# fmc.net
KiCad netlist of a schematic drawn in EAGLE
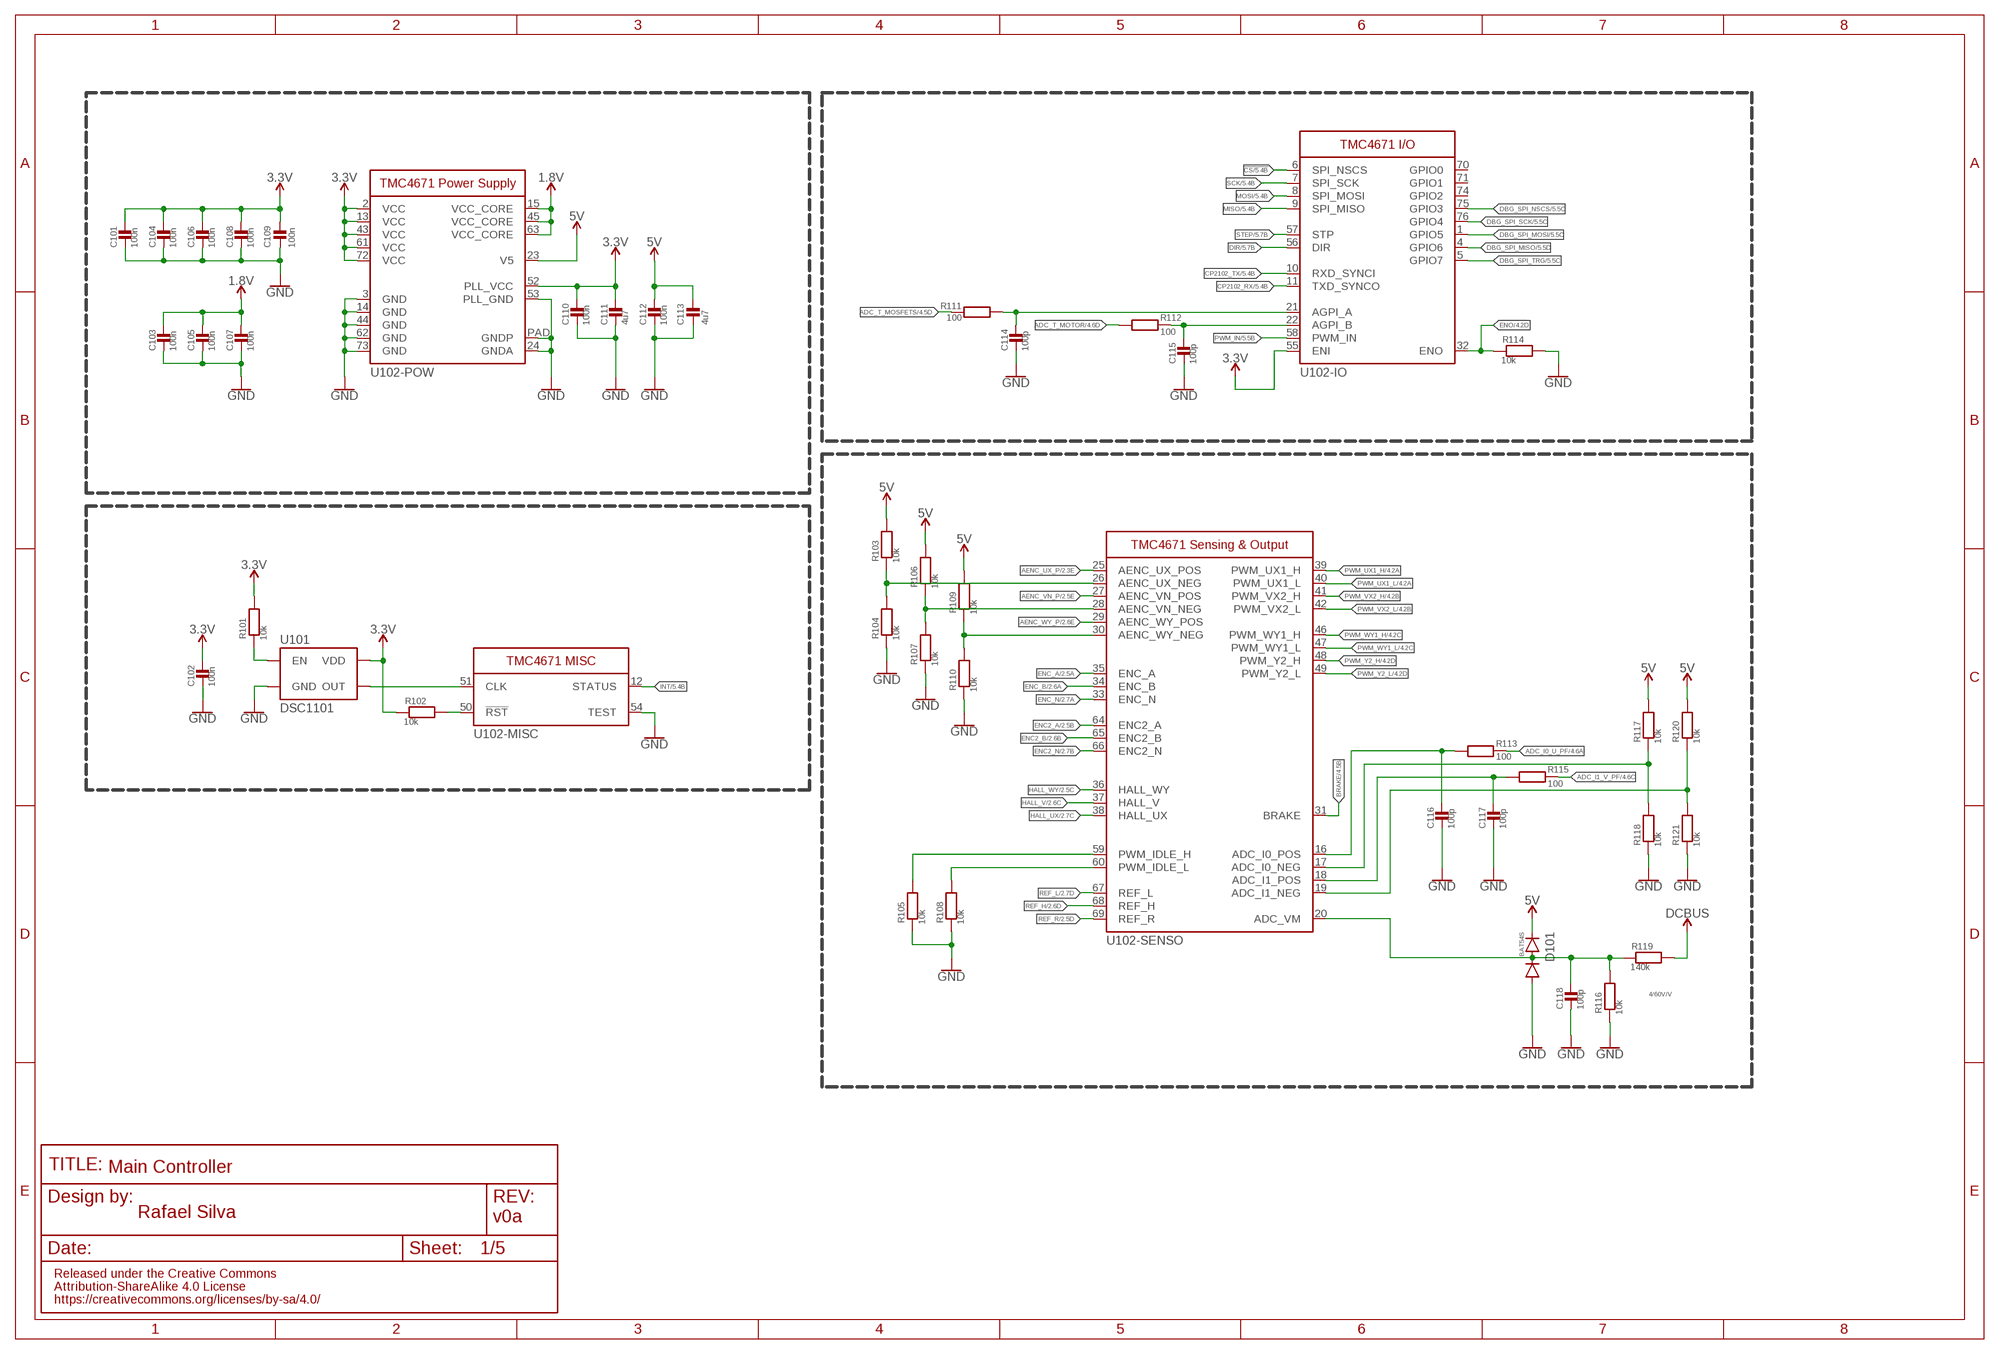
[diagram p0: schematic, sheet 1]
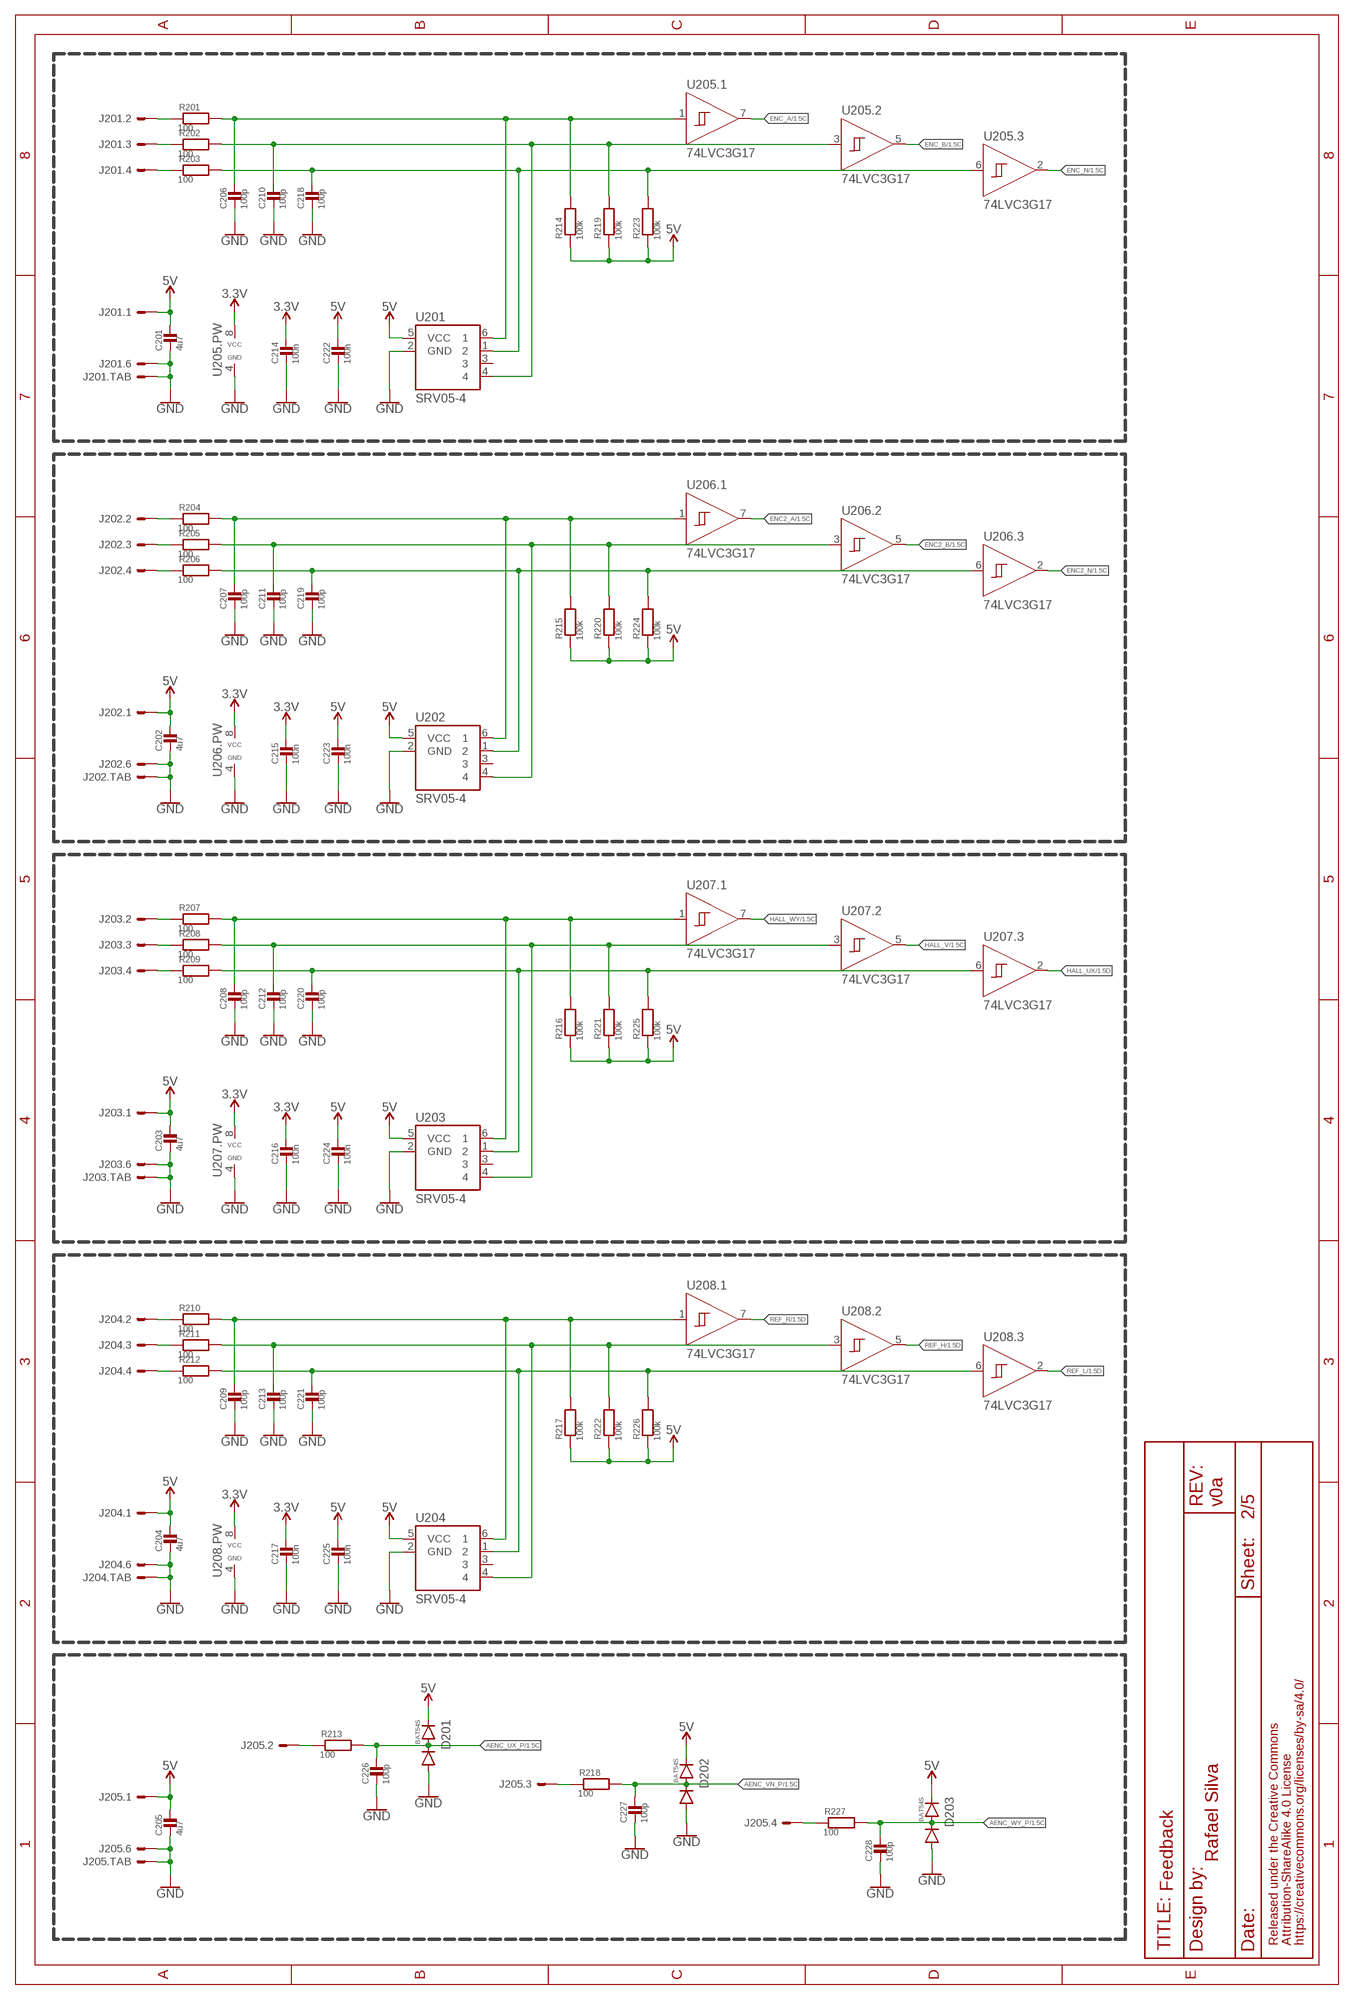
[diagram p1: schematic, sheet 2]
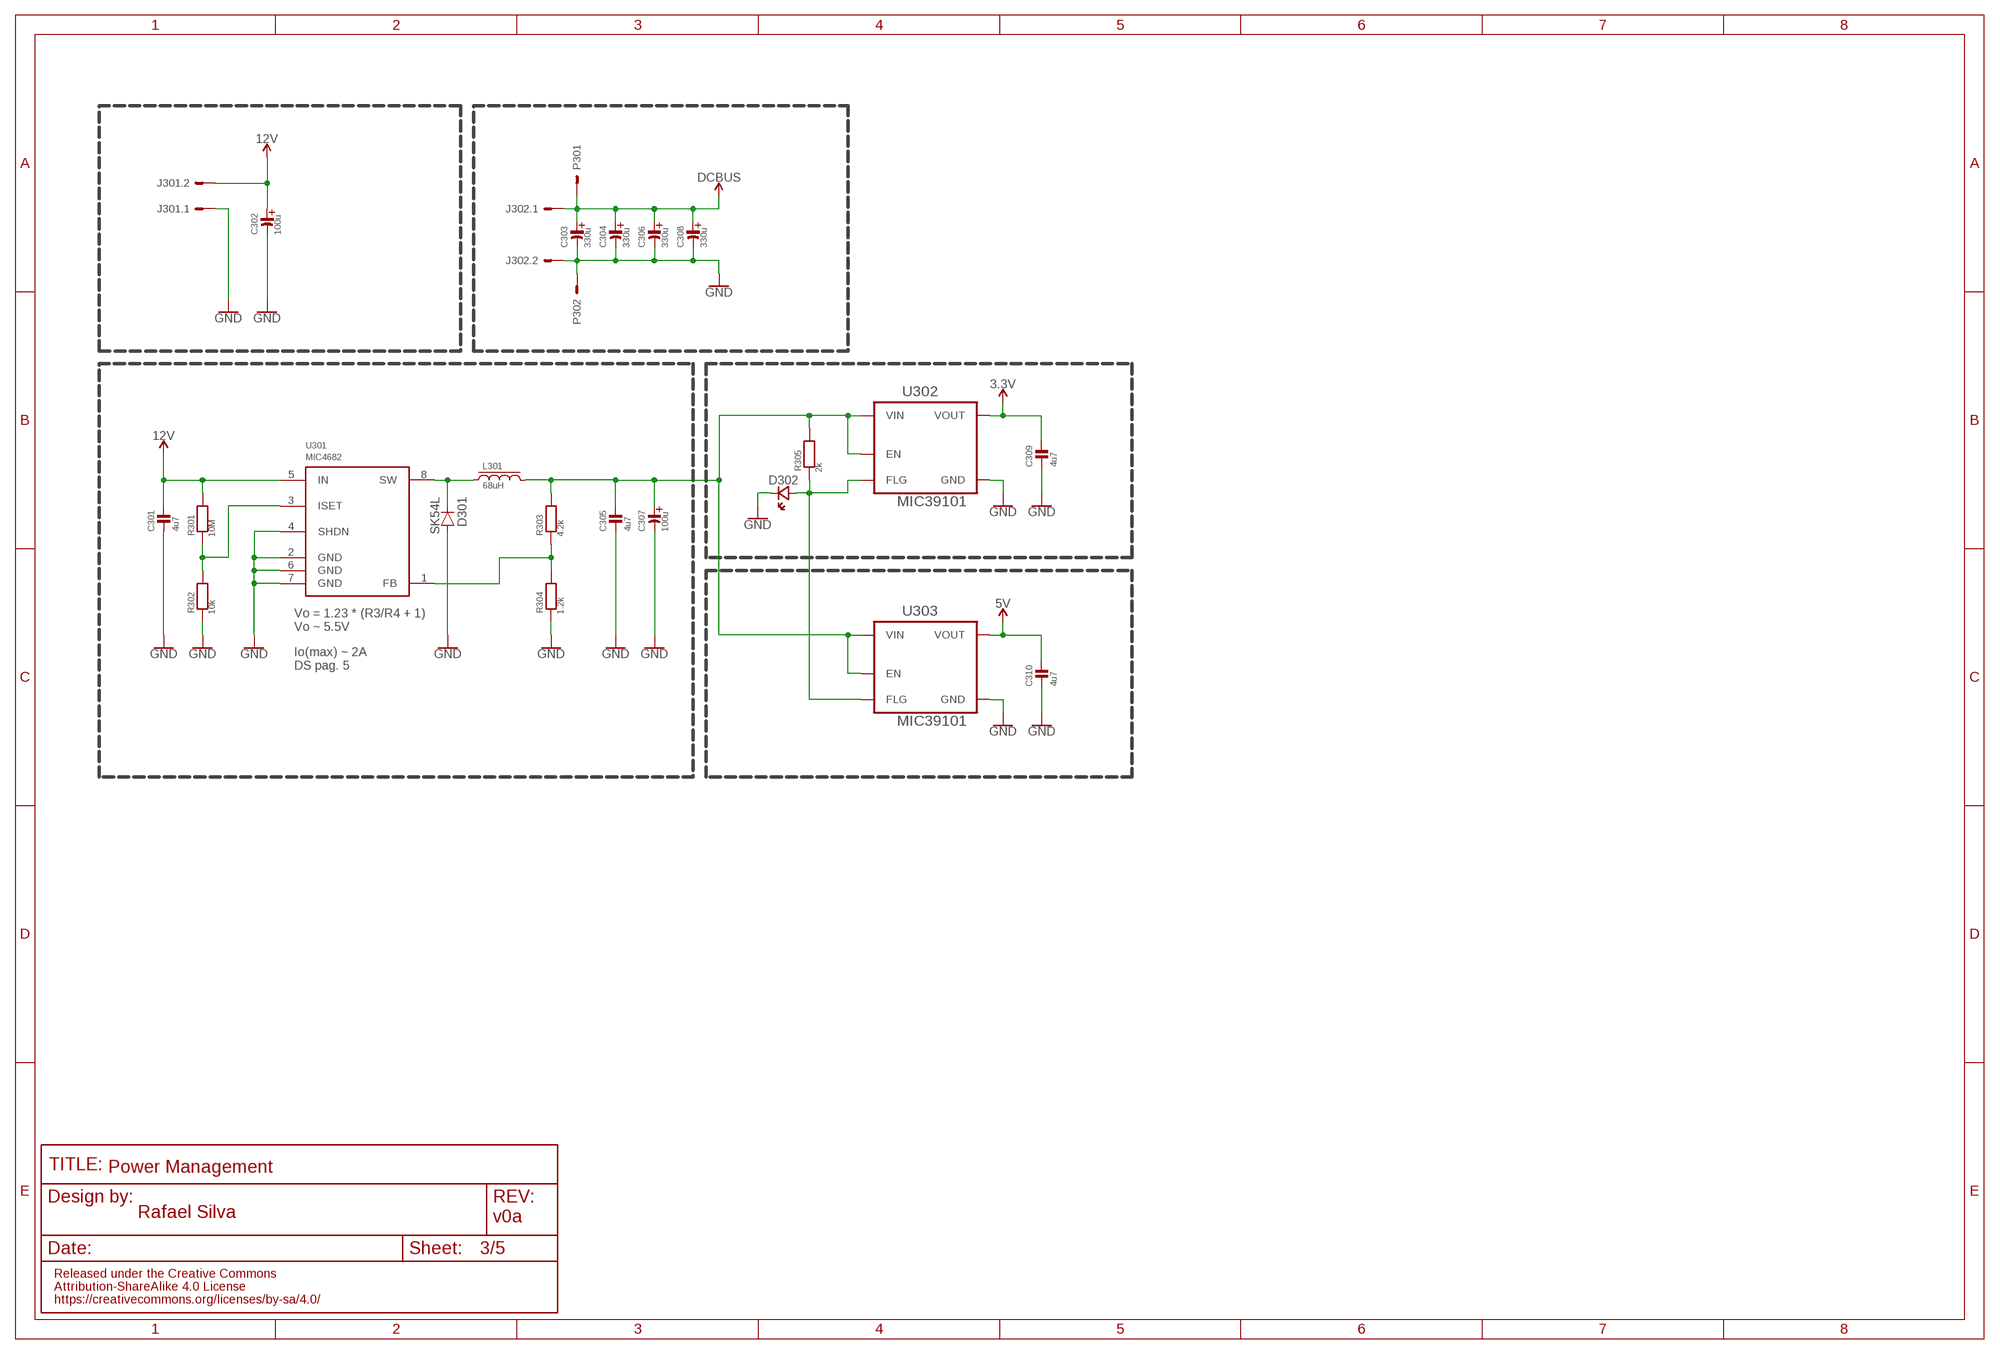
[diagram p2: schematic, sheet 3]
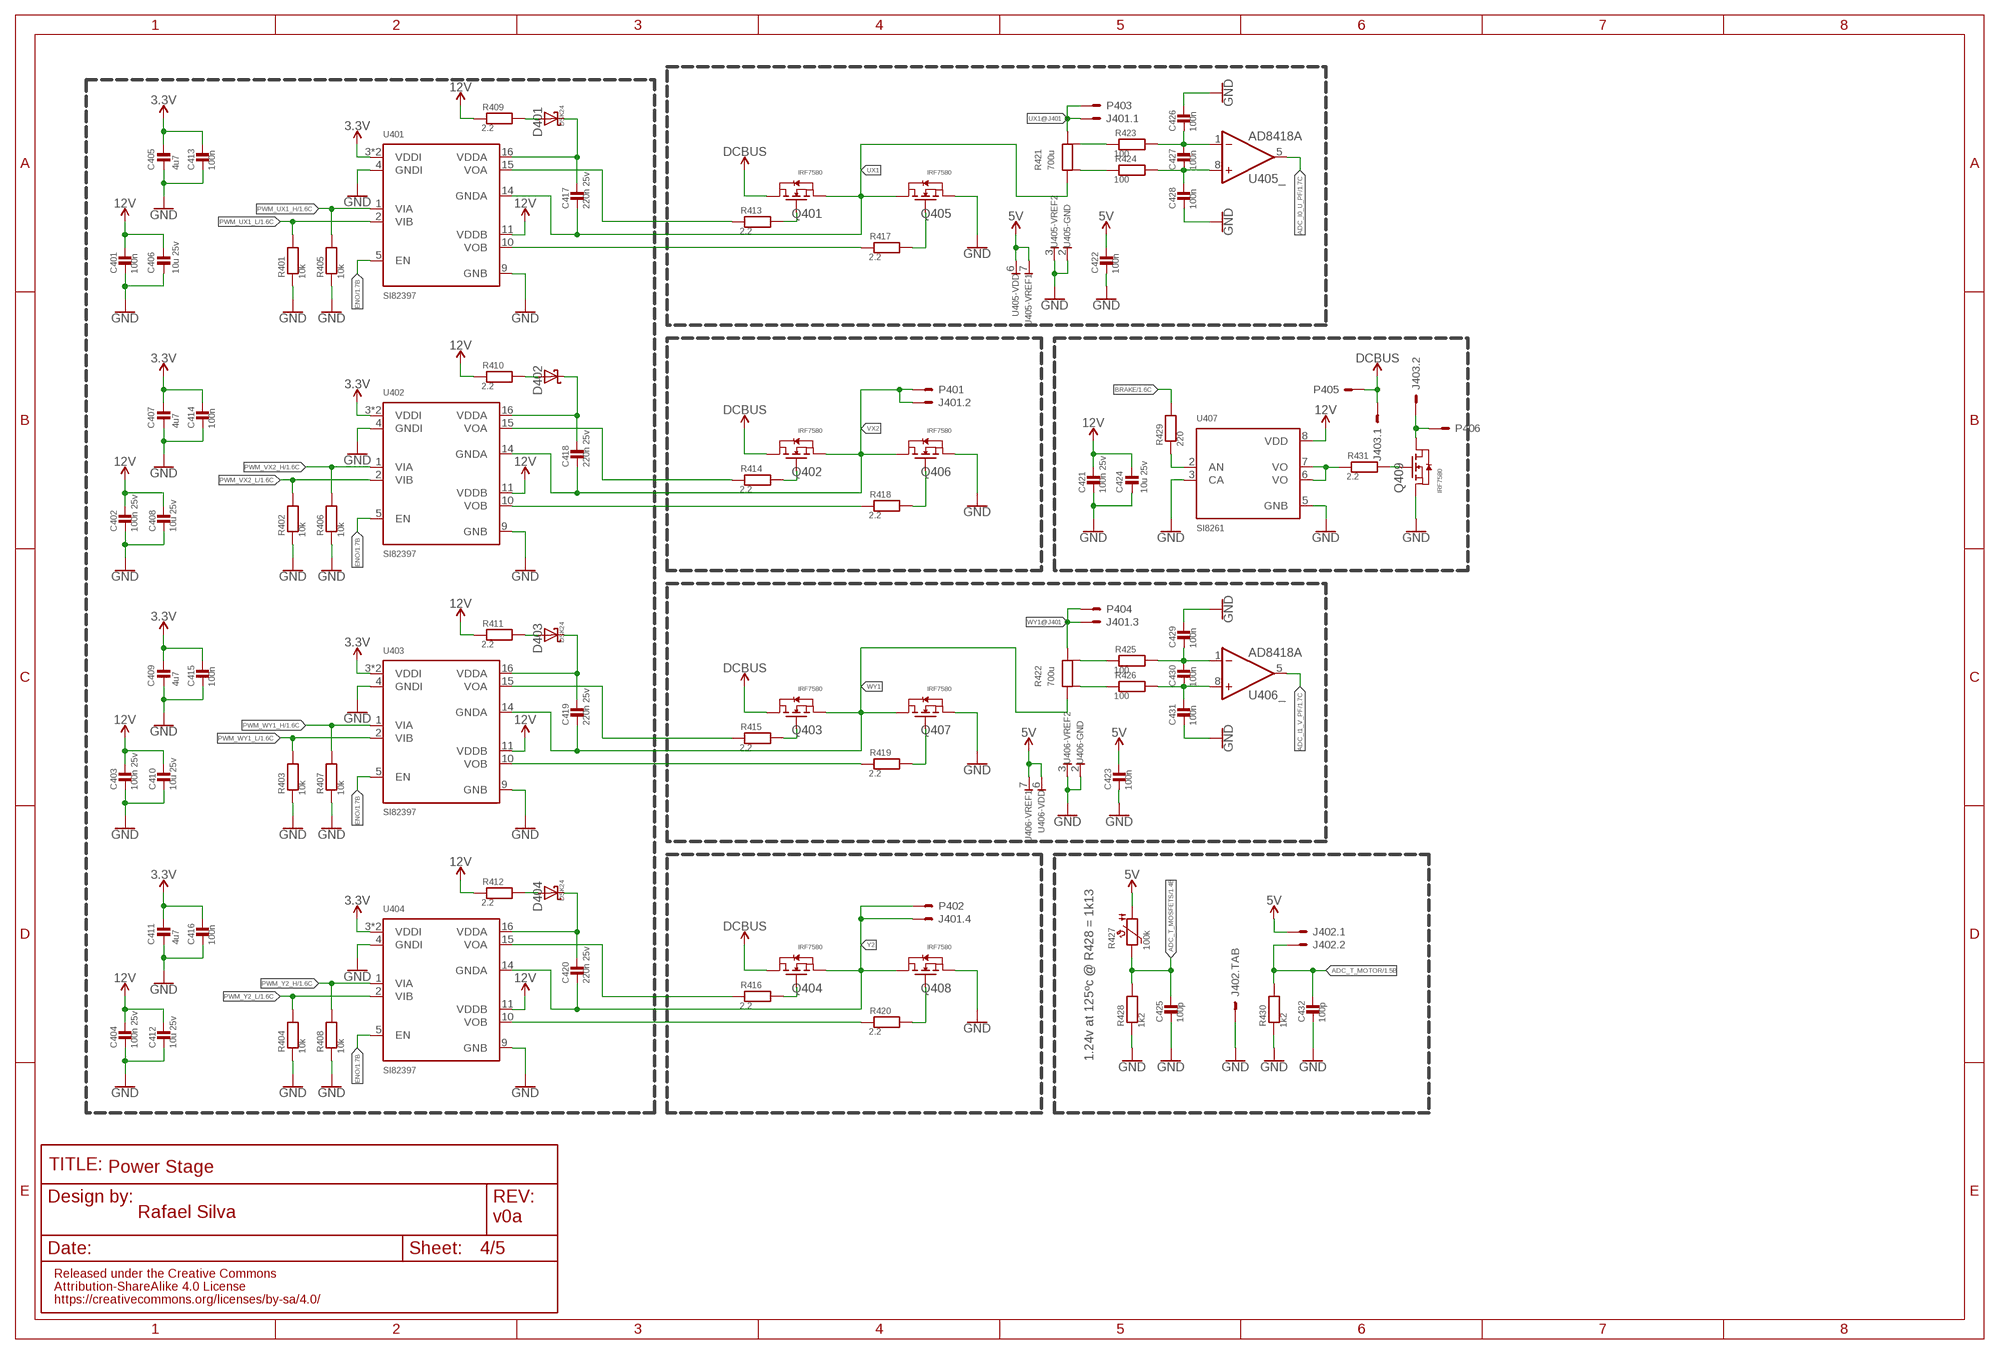
[diagram p3: schematic, sheet 4]
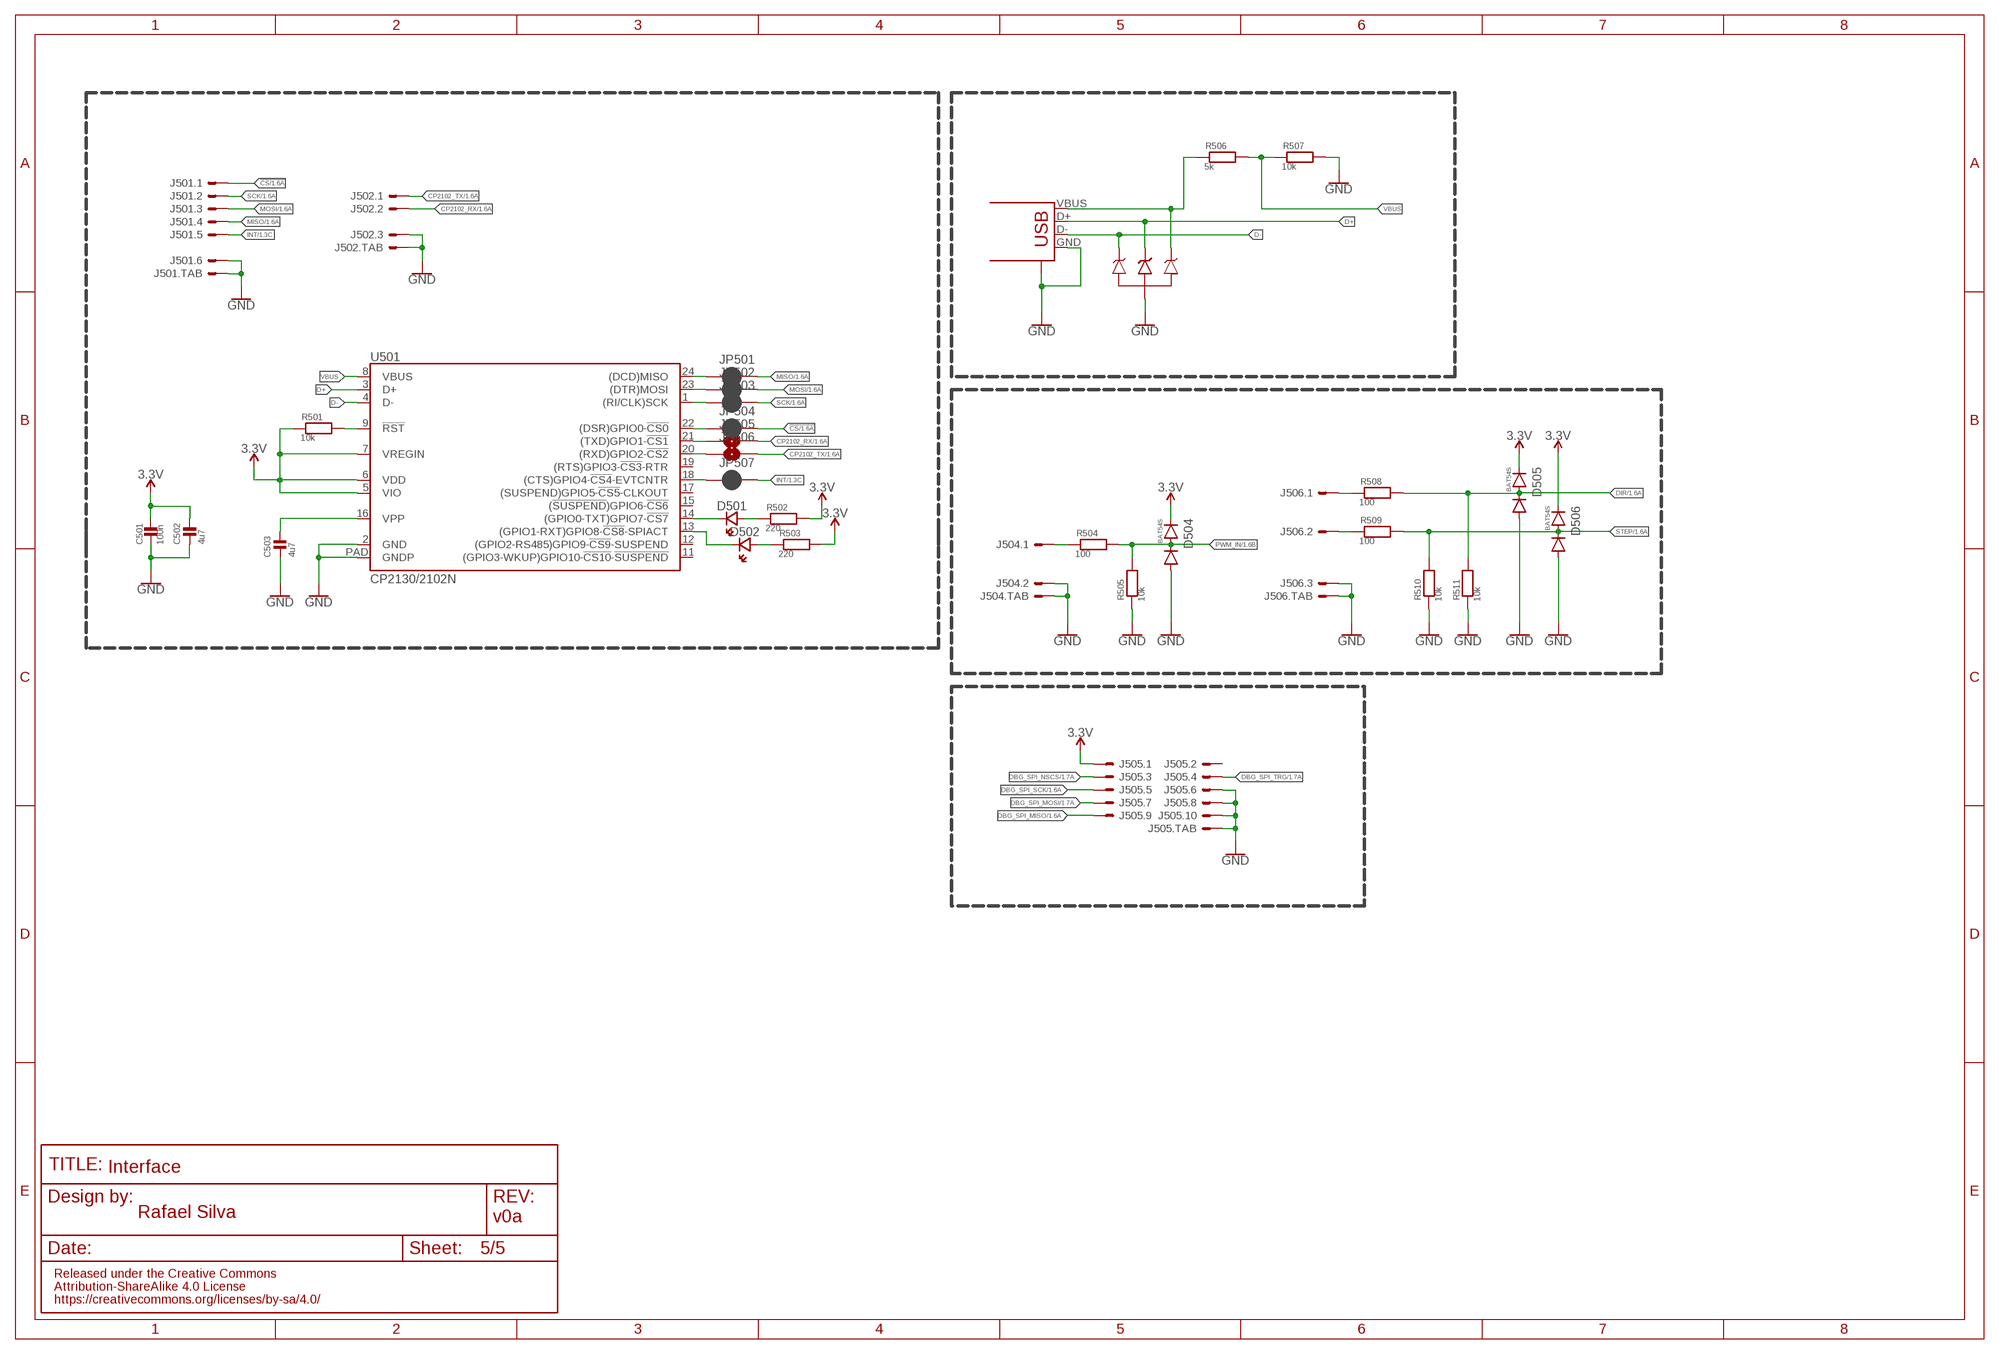
[diagram p4: schematic, sheet 5]

(export (version "E")
  (design (tool "Eeschema 10.0.6"))
  (components
    (comp (ref "C401")
      (value "100n")
      (footprint "eagle-import:0603_WAVE")
      (libsource (lib "eagle-import") (part "MLCC0603"))
    )
    (comp (ref "C402")
      (value "100n 25v")
      (footprint "eagle-import:0603_WAVE")
      (libsource (lib "eagle-import") (part "MLCC0603"))
    )
    (comp (ref "C403")
      (value "100n 25v")
      (footprint "eagle-import:0603_WAVE")
      (libsource (lib "eagle-import") (part "MLCC0603"))
    )
    (comp (ref "C404")
      (value "100n 25v")
      (footprint "eagle-import:0603_WAVE")
      (libsource (lib "eagle-import") (part "MLCC0603"))
    )
    (comp (ref "C405")
      (value "4u7")
      (footprint "eagle-import:0603_WAVE")
      (libsource (lib "eagle-import") (part "MLCC0603"))
    )
    (comp (ref "C406")
      (value "10u 25v")
      (footprint "eagle-import:0603_WAVE")
      (libsource (lib "eagle-import") (part "MLCC0603"))
    )
    (comp (ref "C407")
      (value "4u7")
      (footprint "eagle-import:0603_WAVE")
      (libsource (lib "eagle-import") (part "MLCC0603"))
    )
    (comp (ref "C408")
      (value "10u 25v")
      (footprint "eagle-import:0603_WAVE")
      (libsource (lib "eagle-import") (part "MLCC0603"))
    )
    (comp (ref "C409")
      (value "4u7")
      (footprint "eagle-import:0603_WAVE")
      (libsource (lib "eagle-import") (part "MLCC0603"))
    )
    (comp (ref "C410")
      (value "10u 25v")
      (footprint "eagle-import:0603_WAVE")
      (libsource (lib "eagle-import") (part "MLCC0603"))
    )
    (comp (ref "C411")
      (value "4u7")
      (footprint "eagle-import:0603_WAVE")
      (libsource (lib "eagle-import") (part "MLCC0603"))
    )
    (comp (ref "C412")
      (value "10u 25v")
      (footprint "eagle-import:0603_WAVE")
      (libsource (lib "eagle-import") (part "MLCC0603"))
    )
    (comp (ref "C413")
      (value "100n")
      (footprint "eagle-import:0603_WAVE")
      (libsource (lib "eagle-import") (part "MLCC0603"))
    )
    (comp (ref "C414")
      (value "100n")
      (footprint "eagle-import:0603_WAVE")
      (libsource (lib "eagle-import") (part "MLCC0603"))
    )
    (comp (ref "C415")
      (value "100n")
      (footprint "eagle-import:0603_WAVE")
      (libsource (lib "eagle-import") (part "MLCC0603"))
    )
    (comp (ref "C416")
      (value "100n")
      (footprint "eagle-import:0603_WAVE")
      (libsource (lib "eagle-import") (part "MLCC0603"))
    )
    (comp (ref "C417")
      (value "220n 25v")
      (footprint "eagle-import:0603_WAVE")
      (libsource (lib "eagle-import") (part "MLCC0603"))
    )
    (comp (ref "C418")
      (value "220n 25v")
      (footprint "eagle-import:0603_WAVE")
      (libsource (lib "eagle-import") (part "MLCC0603"))
    )
    (comp (ref "C419")
      (value "220n 25v")
      (footprint "eagle-import:0603_WAVE")
      (libsource (lib "eagle-import") (part "MLCC0603"))
    )
    (comp (ref "C420")
      (value "220n 25v")
      (footprint "eagle-import:0603_WAVE")
      (libsource (lib "eagle-import") (part "MLCC0603"))
    )
    (comp (ref "C421")
      (value "100n 25v")
      (footprint "eagle-import:0603_WAVE")
      (libsource (lib "eagle-import") (part "MLCC0603"))
    )
    (comp (ref "C422")
      (value "100n")
      (footprint "eagle-import:0603_WAVE")
      (libsource (lib "eagle-import") (part "MLCC0603"))
    )
    (comp (ref "C423")
      (value "100n")
      (footprint "eagle-import:0603_WAVE")
      (libsource (lib "eagle-import") (part "MLCC0603"))
    )
    (comp (ref "C424")
      (value "10u 25v")
      (footprint "eagle-import:0603_WAVE")
      (libsource (lib "eagle-import") (part "MLCC0603"))
    )
    (comp (ref "C425")
      (value "100p")
      (footprint "eagle-import:0603_WAVE")
      (libsource (lib "eagle-import") (part "MLCC0603"))
    )
    (comp (ref "C426")
      (value "100n")
      (footprint "eagle-import:0603_WAVE")
      (libsource (lib "eagle-import") (part "MLCC0603"))
    )
    (comp (ref "C427")
      (value "100n")
      (footprint "eagle-import:0603_WAVE")
      (libsource (lib "eagle-import") (part "MLCC0603"))
    )
    (comp (ref "C428")
      (value "100n")
      (footprint "eagle-import:0603_WAVE")
      (libsource (lib "eagle-import") (part "MLCC0603"))
    )
    (comp (ref "C429")
      (value "100n")
      (footprint "eagle-import:0603_WAVE")
      (libsource (lib "eagle-import") (part "MLCC0603"))
    )
    (comp (ref "C430")
      (value "100n")
      (footprint "eagle-import:0603_WAVE")
      (libsource (lib "eagle-import") (part "MLCC0603"))
    )
    (comp (ref "C431")
      (value "100n")
      (footprint "eagle-import:0603_WAVE")
      (libsource (lib "eagle-import") (part "MLCC0603"))
    )
    (comp (ref "C432")
      (value "100p")
      (footprint "eagle-import:0603_WAVE")
      (libsource (lib "eagle-import") (part "MLCC0603"))
    )
    (comp (ref "D401")
      (value "DSK24")
      (footprint "eagle-import:SOD-123")
      (libsource (lib "eagle-import") (part "DSK24"))
    )
    (comp (ref "D402")
      (value "DSK24")
      (footprint "eagle-import:SOD-123")
      (libsource (lib "eagle-import") (part "DSK24"))
    )
    (comp (ref "D403")
      (value "DSK24")
      (footprint "eagle-import:SOD-123")
      (libsource (lib "eagle-import") (part "DSK24"))
    )
    (comp (ref "D404")
      (value "DSK24")
      (footprint "eagle-import:SOD-123")
      (libsource (lib "eagle-import") (part "DSK24"))
    )
    (comp (ref "J401")
      (value "4P-6.35P")
      (footprint "eagle-import:4P-6.35P")
      (libsource (lib "eagle-import") (part "4P-6.35P"))
    )
    (comp (ref "J402")
      (value "SH-2")
      (footprint "eagle-import:SM02B-SSR-H-TB")
      (libsource (lib "eagle-import") (part "SH-2"))
    )
    (comp (ref "J403")
      (value "2P-6.35P")
      (footprint "eagle-import:2P-6.35P")
      (libsource (lib "eagle-import") (part "2P-6.35P"))
    )
    (comp (ref "P401")
      (value "POWPAD")
      (footprint "eagle-import:TH-HP")
      (libsource (lib "eagle-import") (part "POWPAD"))
    )
    (comp (ref "P402")
      (value "POWPAD")
      (footprint "eagle-import:TH-HP")
      (libsource (lib "eagle-import") (part "POWPAD"))
    )
    (comp (ref "P403")
      (value "POWPAD")
      (footprint "eagle-import:TH-HP")
      (libsource (lib "eagle-import") (part "POWPAD"))
    )
    (comp (ref "P404")
      (value "POWPAD")
      (footprint "eagle-import:TH-HP")
      (libsource (lib "eagle-import") (part "POWPAD"))
    )
    (comp (ref "P405")
      (value "POWPAD")
      (footprint "eagle-import:TH-HP")
      (libsource (lib "eagle-import") (part "POWPAD"))
    )
    (comp (ref "P406")
      (value "POWPAD")
      (footprint "eagle-import:TH-HP")
      (libsource (lib "eagle-import") (part "POWPAD"))
    )
    (comp (ref "Q401")
      (value "IRF7580")
      (footprint "eagle-import:DIRECTFET-ME")
      (libsource (lib "eagle-import") (part "IRF7580"))
    )
    (comp (ref "Q402")
      (value "IRF7580")
      (footprint "eagle-import:DIRECTFET-ME")
      (libsource (lib "eagle-import") (part "IRF7580"))
    )
    (comp (ref "Q403")
      (value "IRF7580")
      (footprint "eagle-import:DIRECTFET-ME")
      (libsource (lib "eagle-import") (part "IRF7580"))
    )
    (comp (ref "Q404")
      (value "IRF7580")
      (footprint "eagle-import:DIRECTFET-ME")
      (libsource (lib "eagle-import") (part "IRF7580"))
    )
    (comp (ref "Q405")
      (value "IRF7580")
      (footprint "eagle-import:DIRECTFET-ME")
      (libsource (lib "eagle-import") (part "IRF7580"))
    )
    (comp (ref "Q406")
      (value "IRF7580")
      (footprint "eagle-import:DIRECTFET-ME")
      (libsource (lib "eagle-import") (part "IRF7580"))
    )
    (comp (ref "Q407")
      (value "IRF7580")
      (footprint "eagle-import:DIRECTFET-ME")
      (libsource (lib "eagle-import") (part "IRF7580"))
    )
    (comp (ref "Q408")
      (value "IRF7580")
      (footprint "eagle-import:DIRECTFET-ME")
      (libsource (lib "eagle-import") (part "IRF7580"))
    )
    (comp (ref "Q409")
      (value "IRF7580")
      (footprint "eagle-import:DIRECTFET-ME")
      (libsource (lib "eagle-import") (part "IRF7580"))
    )
    (comp (ref "R401")
      (value "10k")
      (footprint "eagle-import:0603_WAVE")
      (libsource (lib "eagle-import") (part "RESISTOR0603"))
    )
    (comp (ref "R402")
      (value "10k")
      (footprint "eagle-import:0603_WAVE")
      (libsource (lib "eagle-import") (part "RESISTOR0603"))
    )
    (comp (ref "R403")
      (value "10k")
      (footprint "eagle-import:0603_WAVE")
      (libsource (lib "eagle-import") (part "RESISTOR0603"))
    )
    (comp (ref "R404")
      (value "10k")
      (footprint "eagle-import:0603_WAVE")
      (libsource (lib "eagle-import") (part "RESISTOR0603"))
    )
    (comp (ref "R405")
      (value "10k")
      (footprint "eagle-import:0603_WAVE")
      (libsource (lib "eagle-import") (part "RESISTOR0603"))
    )
    (comp (ref "R406")
      (value "10k")
      (footprint "eagle-import:0603_WAVE")
      (libsource (lib "eagle-import") (part "RESISTOR0603"))
    )
    (comp (ref "R407")
      (value "10k")
      (footprint "eagle-import:0603_WAVE")
      (libsource (lib "eagle-import") (part "RESISTOR0603"))
    )
    (comp (ref "R408")
      (value "10k")
      (footprint "eagle-import:0603_WAVE")
      (libsource (lib "eagle-import") (part "RESISTOR0603"))
    )
    (comp (ref "R409")
      (value "2.2")
      (footprint "eagle-import:0603_WAVE")
      (libsource (lib "eagle-import") (part "RESISTOR0603"))
    )
    (comp (ref "R410")
      (value "2.2")
      (footprint "eagle-import:0603_WAVE")
      (libsource (lib "eagle-import") (part "RESISTOR0603"))
    )
    (comp (ref "R411")
      (value "2.2")
      (footprint "eagle-import:0603_WAVE")
      (libsource (lib "eagle-import") (part "RESISTOR0603"))
    )
    (comp (ref "R412")
      (value "2.2")
      (footprint "eagle-import:0603_WAVE")
      (libsource (lib "eagle-import") (part "RESISTOR0603"))
    )
    (comp (ref "R413")
      (value "2.2")
      (footprint "eagle-import:0603_WAVE")
      (libsource (lib "eagle-import") (part "RESISTOR0603"))
    )
    (comp (ref "R414")
      (value "2.2")
      (footprint "eagle-import:0603_WAVE")
      (libsource (lib "eagle-import") (part "RESISTOR0603"))
    )
    (comp (ref "R415")
      (value "2.2")
      (footprint "eagle-import:0603_WAVE")
      (libsource (lib "eagle-import") (part "RESISTOR0603"))
    )
    (comp (ref "R416")
      (value "2.2")
      (footprint "eagle-import:0603_WAVE")
      (libsource (lib "eagle-import") (part "RESISTOR0603"))
    )
    (comp (ref "R417")
      (value "2.2")
      (footprint "eagle-import:0603_WAVE")
      (libsource (lib "eagle-import") (part "RESISTOR0603"))
    )
    (comp (ref "R418")
      (value "2.2")
      (footprint "eagle-import:0603_WAVE")
      (libsource (lib "eagle-import") (part "RESISTOR0603"))
    )
    (comp (ref "R419")
      (value "2.2")
      (footprint "eagle-import:0603_WAVE")
      (libsource (lib "eagle-import") (part "RESISTOR0603"))
    )
    (comp (ref "R420")
      (value "2.2")
      (footprint "eagle-import:0603_WAVE")
      (libsource (lib "eagle-import") (part "RESISTOR0603"))
    )
    (comp (ref "R421")
      (value "700u")
      (footprint "eagle-import:3920")
      (libsource (lib "eagle-import") (part "LRMAP3920"))
    )
    (comp (ref "R422")
      (value "700u")
      (footprint "eagle-import:3920")
      (libsource (lib "eagle-import") (part "LRMAP3920"))
    )
    (comp (ref "R423")
      (value "100")
      (footprint "eagle-import:0603_WAVE")
      (libsource (lib "eagle-import") (part "RESISTOR0603"))
    )
    (comp (ref "R424")
      (value "100")
      (footprint "eagle-import:0603_WAVE")
      (libsource (lib "eagle-import") (part "RESISTOR0603"))
    )
    (comp (ref "R425")
      (value "100")
      (footprint "eagle-import:0603_WAVE")
      (libsource (lib "eagle-import") (part "RESISTOR0603"))
    )
    (comp (ref "R426")
      (value "100")
      (footprint "eagle-import:0603_WAVE")
      (libsource (lib "eagle-import") (part "RESISTOR0603"))
    )
    (comp (ref "R427")
      (value "100k")
      (footprint "eagle-import:0603_WAVE")
      (libsource (lib "eagle-import") (part "NTC0603"))
    )
    (comp (ref "R428")
      (value "1k2")
      (footprint "eagle-import:0603_WAVE")
      (libsource (lib "eagle-import") (part "RESISTOR0603"))
    )
    (comp (ref "R429")
      (value "220")
      (footprint "eagle-import:0603_WAVE")
      (libsource (lib "eagle-import") (part "RESISTOR0603"))
    )
    (comp (ref "R430")
      (value "1k2")
      (footprint "eagle-import:0603_WAVE")
      (libsource (lib "eagle-import") (part "RESISTOR0603"))
    )
    (comp (ref "R431")
      (value "2.2")
      (footprint "eagle-import:0603_WAVE")
      (libsource (lib "eagle-import") (part "RESISTOR0603"))
    )
    (comp (ref "U401")
      (value "SI82397")
      (footprint "eagle-import:SOIC-16-WB")
      (libsource (lib "eagle-import") (part "SI82397"))
    )
    (comp (ref "U402")
      (value "SI82397")
      (footprint "eagle-import:SOIC-16-WB")
      (libsource (lib "eagle-import") (part "SI82397"))
    )
    (comp (ref "U403")
      (value "SI82397")
      (footprint "eagle-import:SOIC-16-WB")
      (libsource (lib "eagle-import") (part "SI82397"))
    )
    (comp (ref "U404")
      (value "SI82397")
      (footprint "eagle-import:SOIC-16-WB")
      (libsource (lib "eagle-import") (part "SI82397"))
    )
    (comp (ref "U405")
      (value "AD8418A")
      (footprint "eagle-import:MSOP-8")
      (libsource (lib "eagle-import") (part "AD8418A"))
    )
    (comp (ref "U406")
      (value "AD8418A")
      (footprint "eagle-import:MSOP-8")
      (libsource (lib "eagle-import") (part "AD8418A"))
    )
    (comp (ref "U407")
      (value "SI8261")
      (footprint "eagle-import:SOIC_8")
      (libsource (lib "eagle-import") (part "SI8261"))
    )
    (comp (ref "C301")
      (value "4u7")
      (footprint "eagle-import:0603_WAVE")
      (libsource (lib "eagle-import") (part "MLCC0603"))
    )
    (comp (ref "C302")
      (value "100u")
      (footprint "eagle-import:PANASONIC_D")
      (libsource (lib "eagle-import") (part "CAPACITOR_ELD"))
    )
    (comp (ref "C303")
      (value "330u")
      (footprint "eagle-import:PANASONIC_G")
      (libsource (lib "eagle-import") (part "CAPACITOR_ELG"))
    )
    (comp (ref "C304")
      (value "330u")
      (footprint "eagle-import:PANASONIC_G")
      (libsource (lib "eagle-import") (part "CAPACITOR_ELG"))
    )
    (comp (ref "C305")
      (value "4u7")
      (footprint "eagle-import:0603_WAVE")
      (libsource (lib "eagle-import") (part "MLCC0603"))
    )
    (comp (ref "C306")
      (value "330u")
      (footprint "eagle-import:PANASONIC_G")
      (libsource (lib "eagle-import") (part "CAPACITOR_ELG"))
    )
    (comp (ref "C307")
      (value "100u")
      (footprint "eagle-import:PANASONIC_D")
      (libsource (lib "eagle-import") (part "CAPACITOR_ELD"))
    )
    (comp (ref "C308")
      (value "330u")
      (footprint "eagle-import:PANASONIC_G")
      (libsource (lib "eagle-import") (part "CAPACITOR_ELG"))
    )
    (comp (ref "C309")
      (value "4u7")
      (footprint "eagle-import:0603_WAVE")
      (libsource (lib "eagle-import") (part "MLCC0603"))
    )
    (comp (ref "C310")
      (value "4u7")
      (footprint "eagle-import:0603_WAVE")
      (libsource (lib "eagle-import") (part "MLCC0603"))
    )
    (comp (ref "D301")
      (value "SK54L")
      (footprint "eagle-import:DO214AA")
      (libsource (lib "eagle-import") (part "SK54L"))
    )
    (comp (ref "D302")
      (value "LED0603")
      (footprint "eagle-import:CHIPLED_0603")
      (libsource (lib "eagle-import") (part "LED0603"))
    )
    (comp (ref "J301")
      (value "2P-6.35P")
      (footprint "eagle-import:2P-6.35P")
      (libsource (lib "eagle-import") (part "2P-6.35P"))
    )
    (comp (ref "J302")
      (value "2P-6.35P")
      (footprint "eagle-import:2P-6.35P")
      (libsource (lib "eagle-import") (part "2P-6.35P"))
    )
    (comp (ref "L301")
      (value "68uH")
      (footprint "eagle-import:CDRH104R")
      (libsource (lib "eagle-import") (part "INDUCTORCDRH104R"))
    )
    (comp (ref "P301")
      (value "POWPAD")
      (footprint "eagle-import:TH-HP")
      (libsource (lib "eagle-import") (part "POWPAD"))
    )
    (comp (ref "P302")
      (value "POWPAD")
      (footprint "eagle-import:TH-HP")
      (libsource (lib "eagle-import") (part "POWPAD"))
    )
    (comp (ref "R301")
      (value "10M")
      (footprint "eagle-import:0603_WAVE")
      (libsource (lib "eagle-import") (part "RESISTOR0603"))
    )
    (comp (ref "R302")
      (value "10k")
      (footprint "eagle-import:0603_WAVE")
      (libsource (lib "eagle-import") (part "RESISTOR0603"))
    )
    (comp (ref "R303")
      (value "4.2k")
      (footprint "eagle-import:0603_WAVE")
      (libsource (lib "eagle-import") (part "RESISTOR0603"))
    )
    (comp (ref "R304")
      (value "1.2k")
      (footprint "eagle-import:0603_WAVE")
      (libsource (lib "eagle-import") (part "RESISTOR0603"))
    )
    (comp (ref "R305")
      (value "2k")
      (footprint "eagle-import:0603_WAVE")
      (libsource (lib "eagle-import") (part "RESISTOR0603"))
    )
    (comp (ref "U301")
      (value "MIC4682")
      (footprint "eagle-import:SOIC8")
      (libsource (lib "eagle-import") (part "MIC4682"))
    )
    (comp (ref "U302")
      (value "MIC39101")
      (footprint "eagle-import:SOIC8")
      (libsource (lib "eagle-import") (part "MIC39101"))
    )
    (comp (ref "U303")
      (value "MIC39101")
      (footprint "eagle-import:SOIC8")
      (libsource (lib "eagle-import") (part "MIC39101"))
    )
    (comp (ref "C501")
      (value "100n")
      (footprint "eagle-import:0603_WAVE")
      (libsource (lib "eagle-import") (part "MLCC0603"))
    )
    (comp (ref "C502")
      (value "4u7")
      (footprint "eagle-import:0603_WAVE")
      (libsource (lib "eagle-import") (part "MLCC0603"))
    )
    (comp (ref "C503")
      (value "4u7")
      (footprint "eagle-import:0603_WAVE")
      (libsource (lib "eagle-import") (part "MLCC0603"))
    )
    (comp (ref "D501")
      (value "LED0603")
      (footprint "eagle-import:CHIPLED_0603")
      (libsource (lib "eagle-import") (part "LED0603"))
    )
    (comp (ref "D502")
      (value "LED0603")
      (footprint "eagle-import:CHIPLED_0603")
      (libsource (lib "eagle-import") (part "LED0603"))
    )
    (comp (ref "D503")
      (value "SP0503BAHT")
      (footprint "eagle-import:SOT143")
      (libsource (lib "eagle-import") (part "SP0503BAHT"))
    )
    (comp (ref "D504")
      (value "BAT54S")
      (footprint "eagle-import:SOT-23-3")
      (libsource (lib "eagle-import") (part "BAT54S"))
    )
    (comp (ref "D505")
      (value "BAT54S")
      (footprint "eagle-import:SOT-23-3")
      (libsource (lib "eagle-import") (part "BAT54S"))
    )
    (comp (ref "D506")
      (value "BAT54S")
      (footprint "eagle-import:SOT-23-3")
      (libsource (lib "eagle-import") (part "BAT54S"))
    )
    (comp (ref "J501")
      (value "SH-6")
      (footprint "eagle-import:SM06B-SSR-H-TB")
      (libsource (lib "eagle-import") (part "SH-6"))
    )
    (comp (ref "J502")
      (value "SH-3")
      (footprint "eagle-import:SM03B-SSR-H-TB")
      (libsource (lib "eagle-import") (part "SH-3"))
    )
    (comp (ref "J503")
      (value "USB-SHIELD")
      (footprint "eagle-import:USB-M-S1")
      (libsource (lib "eagle-import") (part "USB-SHIELD"))
    )
    (comp (ref "J504")
      (value "SH-2")
      (footprint "eagle-import:SM02B-SSR-H-TB")
      (libsource (lib "eagle-import") (part "SH-2"))
    )
    (comp (ref "J505")
      (value "F20F-10DP-1V")
      (footprint "eagle-import:F20F-10DP-1V")
      (libsource (lib "eagle-import") (part "F20F-10DP-1V"))
    )
    (comp (ref "J506")
      (value "SH-3")
      (footprint "eagle-import:SM03B-SSR-H-TB")
      (libsource (lib "eagle-import") (part "SH-3"))
    )
    (comp (ref "JP501")
      (value "JUMPER-SMT_2_NC_PASTE_SILK")
      (footprint "eagle-import:SMT-JUMPER_2_NC_PASTE_SILK")
      (libsource (lib "eagle-import") (part "JUMPER-SMT_2_NC_PASTE_SILK"))
    )
    (comp (ref "JP502")
      (value "JUMPER-SMT_2_NC_PASTE_SILK")
      (footprint "eagle-import:SMT-JUMPER_2_NC_PASTE_SILK")
      (libsource (lib "eagle-import") (part "JUMPER-SMT_2_NC_PASTE_SILK"))
    )
    (comp (ref "JP503")
      (value "JUMPER-SMT_2_NC_PASTE_SILK")
      (footprint "eagle-import:SMT-JUMPER_2_NC_PASTE_SILK")
      (libsource (lib "eagle-import") (part "JUMPER-SMT_2_NC_PASTE_SILK"))
    )
    (comp (ref "JP504")
      (value "JUMPER-SMT_2_NC_PASTE_SILK")
      (footprint "eagle-import:SMT-JUMPER_2_NC_PASTE_SILK")
      (libsource (lib "eagle-import") (part "JUMPER-SMT_2_NC_PASTE_SILK"))
    )
    (comp (ref "JP505")
      (value "JUMPER-SMT_2_NO_SILK")
      (footprint "eagle-import:SMT-JUMPER_2_NO_SILK")
      (libsource (lib "eagle-import") (part "JUMPER-SMT_2_NO_SILK"))
    )
    (comp (ref "JP506")
      (value "JUMPER-SMT_2_NO_SILK")
      (footprint "eagle-import:SMT-JUMPER_2_NO_SILK")
      (libsource (lib "eagle-import") (part "JUMPER-SMT_2_NO_SILK"))
    )
    (comp (ref "JP507")
      (value "JUMPER-SMT_2_NC_PASTE_SILK")
      (footprint "eagle-import:SMT-JUMPER_2_NC_PASTE_SILK")
      (libsource (lib "eagle-import") (part "JUMPER-SMT_2_NC_PASTE_SILK"))
    )
    (comp (ref "R501")
      (value "10k")
      (footprint "eagle-import:0603_WAVE")
      (libsource (lib "eagle-import") (part "RESISTOR0603"))
    )
    (comp (ref "R502")
      (value "220")
      (footprint "eagle-import:0603_WAVE")
      (libsource (lib "eagle-import") (part "RESISTOR0603"))
    )
    (comp (ref "R503")
      (value "220")
      (footprint "eagle-import:0603_WAVE")
      (libsource (lib "eagle-import") (part "RESISTOR0603"))
    )
    (comp (ref "R504")
      (value "100")
      (footprint "eagle-import:0603_WAVE")
      (libsource (lib "eagle-import") (part "RESISTOR0603"))
    )
    (comp (ref "R505")
      (value "10k")
      (footprint "eagle-import:0603_WAVE")
      (libsource (lib "eagle-import") (part "RESISTOR0603"))
    )
    (comp (ref "R506")
      (value "5k")
      (footprint "eagle-import:0603_WAVE")
      (libsource (lib "eagle-import") (part "RESISTOR0603"))
    )
    (comp (ref "R507")
      (value "10k")
      (footprint "eagle-import:0603_WAVE")
      (libsource (lib "eagle-import") (part "RESISTOR0603"))
    )
    (comp (ref "R508")
      (value "100")
      (footprint "eagle-import:0603_WAVE")
      (libsource (lib "eagle-import") (part "RESISTOR0603"))
    )
    (comp (ref "R509")
      (value "100")
      (footprint "eagle-import:0603_WAVE")
      (libsource (lib "eagle-import") (part "RESISTOR0603"))
    )
    (comp (ref "R510")
      (value "10k")
      (footprint "eagle-import:0603_WAVE")
      (libsource (lib "eagle-import") (part "RESISTOR0603"))
    )
    (comp (ref "R511")
      (value "10k")
      (footprint "eagle-import:0603_WAVE")
      (libsource (lib "eagle-import") (part "RESISTOR0603"))
    )
    (comp (ref "U501")
      (value "CP2130/2102N")
      (footprint "eagle-import:QFN24")
      (libsource (lib "eagle-import") (part "CP2130/2102N"))
    )
    (comp (ref "C201")
      (value "4u7")
      (footprint "eagle-import:0603_WAVE")
      (libsource (lib "eagle-import") (part "MLCC0603"))
    )
    (comp (ref "C202")
      (value "4u7")
      (footprint "eagle-import:0603_WAVE")
      (libsource (lib "eagle-import") (part "MLCC0603"))
    )
    (comp (ref "C203")
      (value "4u7")
      (footprint "eagle-import:0603_WAVE")
      (libsource (lib "eagle-import") (part "MLCC0603"))
    )
    (comp (ref "C204")
      (value "4u7")
      (footprint "eagle-import:0603_WAVE")
      (libsource (lib "eagle-import") (part "MLCC0603"))
    )
    (comp (ref "C205")
      (value "4u7")
      (footprint "eagle-import:0603_WAVE")
      (libsource (lib "eagle-import") (part "MLCC0603"))
    )
    (comp (ref "C206")
      (value "100p")
      (footprint "eagle-import:0603_WAVE")
      (libsource (lib "eagle-import") (part "MLCC0603"))
    )
    (comp (ref "C207")
      (value "100p")
      (footprint "eagle-import:0603_WAVE")
      (libsource (lib "eagle-import") (part "MLCC0603"))
    )
    (comp (ref "C208")
      (value "100p")
      (footprint "eagle-import:0603_WAVE")
      (libsource (lib "eagle-import") (part "MLCC0603"))
    )
    (comp (ref "C209")
      (value "100p")
      (footprint "eagle-import:0603_WAVE")
      (libsource (lib "eagle-import") (part "MLCC0603"))
    )
    (comp (ref "C210")
      (value "100p")
      (footprint "eagle-import:0603_WAVE")
      (libsource (lib "eagle-import") (part "MLCC0603"))
    )
    (comp (ref "C211")
      (value "100p")
      (footprint "eagle-import:0603_WAVE")
      (libsource (lib "eagle-import") (part "MLCC0603"))
    )
    (comp (ref "C212")
      (value "100p")
      (footprint "eagle-import:0603_WAVE")
      (libsource (lib "eagle-import") (part "MLCC0603"))
    )
    (comp (ref "C213")
      (value "100p")
      (footprint "eagle-import:0603_WAVE")
      (libsource (lib "eagle-import") (part "MLCC0603"))
    )
    (comp (ref "C214")
      (value "100n")
      (footprint "eagle-import:0603_WAVE")
      (libsource (lib "eagle-import") (part "MLCC0603"))
    )
    (comp (ref "C215")
      (value "100n")
      (footprint "eagle-import:0603_WAVE")
      (libsource (lib "eagle-import") (part "MLCC0603"))
    )
    (comp (ref "C216")
      (value "100n")
      (footprint "eagle-import:0603_WAVE")
      (libsource (lib "eagle-import") (part "MLCC0603"))
    )
    (comp (ref "C217")
      (value "100n")
      (footprint "eagle-import:0603_WAVE")
      (libsource (lib "eagle-import") (part "MLCC0603"))
    )
    (comp (ref "C218")
      (value "100p")
      (footprint "eagle-import:0603_WAVE")
      (libsource (lib "eagle-import") (part "MLCC0603"))
    )
    (comp (ref "C219")
      (value "100p")
      (footprint "eagle-import:0603_WAVE")
      (libsource (lib "eagle-import") (part "MLCC0603"))
    )
    (comp (ref "C220")
      (value "100p")
      (footprint "eagle-import:0603_WAVE")
      (libsource (lib "eagle-import") (part "MLCC0603"))
    )
    (comp (ref "C221")
      (value "100p")
      (footprint "eagle-import:0603_WAVE")
      (libsource (lib "eagle-import") (part "MLCC0603"))
    )
    (comp (ref "C222")
      (value "100n")
      (footprint "eagle-import:0603_WAVE")
      (libsource (lib "eagle-import") (part "MLCC0603"))
    )
    (comp (ref "C223")
      (value "100n")
      (footprint "eagle-import:0603_WAVE")
      (libsource (lib "eagle-import") (part "MLCC0603"))
    )
    (comp (ref "C224")
      (value "100n")
      (footprint "eagle-import:0603_WAVE")
      (libsource (lib "eagle-import") (part "MLCC0603"))
    )
    (comp (ref "C225")
      (value "100n")
      (footprint "eagle-import:0603_WAVE")
      (libsource (lib "eagle-import") (part "MLCC0603"))
    )
    (comp (ref "C226")
      (value "100p")
      (footprint "eagle-import:0603_WAVE")
      (libsource (lib "eagle-import") (part "MLCC0603"))
    )
    (comp (ref "C227")
      (value "100p")
      (footprint "eagle-import:0603_WAVE")
      (libsource (lib "eagle-import") (part "MLCC0603"))
    )
    (comp (ref "C228")
      (value "100p")
      (footprint "eagle-import:0603_WAVE")
      (libsource (lib "eagle-import") (part "MLCC0603"))
    )
    (comp (ref "D201")
      (value "BAT54S")
      (footprint "eagle-import:SOT-23-3")
      (libsource (lib "eagle-import") (part "BAT54S"))
    )
    (comp (ref "D202")
      (value "BAT54S")
      (footprint "eagle-import:SOT-23-3")
      (libsource (lib "eagle-import") (part "BAT54S"))
    )
    (comp (ref "D203")
      (value "BAT54S")
      (footprint "eagle-import:SOT-23-3")
      (libsource (lib "eagle-import") (part "BAT54S"))
    )
    (comp (ref "J201")
      (value "SH-5")
      (footprint "eagle-import:SM05B-SSR-H-TB")
      (libsource (lib "eagle-import") (part "SH-5"))
    )
    (comp (ref "J202")
      (value "SH-5")
      (footprint "eagle-import:SM05B-SSR-H-TB")
      (libsource (lib "eagle-import") (part "SH-5"))
    )
    (comp (ref "J203")
      (value "SH-5")
      (footprint "eagle-import:SM05B-SSR-H-TB")
      (libsource (lib "eagle-import") (part "SH-5"))
    )
    (comp (ref "J204")
      (value "SH-5")
      (footprint "eagle-import:SM05B-SSR-H-TB")
      (libsource (lib "eagle-import") (part "SH-5"))
    )
    (comp (ref "J205")
      (value "SH-5")
      (footprint "eagle-import:SM05B-SSR-H-TB")
      (libsource (lib "eagle-import") (part "SH-5"))
    )
    (comp (ref "R201")
      (value "100")
      (footprint "eagle-import:0603_WAVE")
      (libsource (lib "eagle-import") (part "RESISTOR0603"))
    )
    (comp (ref "R202")
      (value "100")
      (footprint "eagle-import:0603_WAVE")
      (libsource (lib "eagle-import") (part "RESISTOR0603"))
    )
    (comp (ref "R203")
      (value "100")
      (footprint "eagle-import:0603_WAVE")
      (libsource (lib "eagle-import") (part "RESISTOR0603"))
    )
    (comp (ref "R204")
      (value "100")
      (footprint "eagle-import:0603_WAVE")
      (libsource (lib "eagle-import") (part "RESISTOR0603"))
    )
    (comp (ref "R205")
      (value "100")
      (footprint "eagle-import:0603_WAVE")
      (libsource (lib "eagle-import") (part "RESISTOR0603"))
    )
    (comp (ref "R206")
      (value "100")
      (footprint "eagle-import:0603_WAVE")
      (libsource (lib "eagle-import") (part "RESISTOR0603"))
    )
    (comp (ref "R207")
      (value "100")
      (footprint "eagle-import:0603_WAVE")
      (libsource (lib "eagle-import") (part "RESISTOR0603"))
    )
    (comp (ref "R208")
      (value "100")
      (footprint "eagle-import:0603_WAVE")
      (libsource (lib "eagle-import") (part "RESISTOR0603"))
    )
    (comp (ref "R209")
      (value "100")
      (footprint "eagle-import:0603_WAVE")
      (libsource (lib "eagle-import") (part "RESISTOR0603"))
    )
    (comp (ref "R210")
      (value "100")
      (footprint "eagle-import:0603_WAVE")
      (libsource (lib "eagle-import") (part "RESISTOR0603"))
    )
    (comp (ref "R211")
      (value "100")
      (footprint "eagle-import:0603_WAVE")
      (libsource (lib "eagle-import") (part "RESISTOR0603"))
    )
    (comp (ref "R212")
      (value "100")
      (footprint "eagle-import:0603_WAVE")
      (libsource (lib "eagle-import") (part "RESISTOR0603"))
    )
    (comp (ref "R213")
      (value "100")
      (footprint "eagle-import:0603_WAVE")
      (libsource (lib "eagle-import") (part "RESISTOR0603"))
    )
    (comp (ref "R214")
      (value "100k")
      (footprint "eagle-import:0603_WAVE")
      (libsource (lib "eagle-import") (part "RESISTOR0603"))
    )
    (comp (ref "R215")
      (value "100k")
      (footprint "eagle-import:0603_WAVE")
      (libsource (lib "eagle-import") (part "RESISTOR0603"))
    )
    (comp (ref "R216")
      (value "100k")
      (footprint "eagle-import:0603_WAVE")
      (libsource (lib "eagle-import") (part "RESISTOR0603"))
    )
    (comp (ref "R217")
      (value "100k")
      (footprint "eagle-import:0603_WAVE")
      (libsource (lib "eagle-import") (part "RESISTOR0603"))
    )
    (comp (ref "R218")
      (value "100")
      (footprint "eagle-import:0603_WAVE")
      (libsource (lib "eagle-import") (part "RESISTOR0603"))
    )
    (comp (ref "R219")
      (value "100k")
      (footprint "eagle-import:0603_WAVE")
      (libsource (lib "eagle-import") (part "RESISTOR0603"))
    )
    (comp (ref "R220")
      (value "100k")
      (footprint "eagle-import:0603_WAVE")
      (libsource (lib "eagle-import") (part "RESISTOR0603"))
    )
    (comp (ref "R221")
      (value "100k")
      (footprint "eagle-import:0603_WAVE")
      (libsource (lib "eagle-import") (part "RESISTOR0603"))
    )
    (comp (ref "R222")
      (value "100k")
      (footprint "eagle-import:0603_WAVE")
      (libsource (lib "eagle-import") (part "RESISTOR0603"))
    )
    (comp (ref "R223")
      (value "100k")
      (footprint "eagle-import:0603_WAVE")
      (libsource (lib "eagle-import") (part "RESISTOR0603"))
    )
    (comp (ref "R224")
      (value "100k")
      (footprint "eagle-import:0603_WAVE")
      (libsource (lib "eagle-import") (part "RESISTOR0603"))
    )
    (comp (ref "R225")
      (value "100k")
      (footprint "eagle-import:0603_WAVE")
      (libsource (lib "eagle-import") (part "RESISTOR0603"))
    )
    (comp (ref "R226")
      (value "100k")
      (footprint "eagle-import:0603_WAVE")
      (libsource (lib "eagle-import") (part "RESISTOR0603"))
    )
    (comp (ref "R227")
      (value "100")
      (footprint "eagle-import:0603_WAVE")
      (libsource (lib "eagle-import") (part "RESISTOR0603"))
    )
    (comp (ref "U201")
      (value "SRV05-4")
      (footprint "eagle-import:SOT23-6")
      (libsource (lib "eagle-import") (part "SRV05-4"))
    )
    (comp (ref "U202")
      (value "SRV05-4")
      (footprint "eagle-import:SOT23-6")
      (libsource (lib "eagle-import") (part "SRV05-4"))
    )
    (comp (ref "U203")
      (value "SRV05-4")
      (footprint "eagle-import:SOT23-6")
      (libsource (lib "eagle-import") (part "SRV05-4"))
    )
    (comp (ref "U204")
      (value "SRV05-4")
      (footprint "eagle-import:SOT23-6")
      (libsource (lib "eagle-import") (part "SRV05-4"))
    )
    (comp (ref "U205")
      (value "74LVC3G17")
      (footprint "eagle-import:TSSOP-8")
      (libsource (lib "eagle-import") (part "74LVC3G17"))
    )
    (comp (ref "U206")
      (value "74LVC3G17")
      (footprint "eagle-import:TSSOP-8")
      (libsource (lib "eagle-import") (part "74LVC3G17"))
    )
    (comp (ref "U207")
      (value "74LVC3G17")
      (footprint "eagle-import:TSSOP-8")
      (libsource (lib "eagle-import") (part "74LVC3G17"))
    )
    (comp (ref "U208")
      (value "74LVC3G17")
      (footprint "eagle-import:TSSOP-8")
      (libsource (lib "eagle-import") (part "74LVC3G17"))
    )
    (comp (ref "C101")
      (value "100n")
      (footprint "eagle-import:0603_WAVE")
      (libsource (lib "eagle-import") (part "MLCC0603"))
    )
    (comp (ref "C102")
      (value "100n")
      (footprint "eagle-import:0603_WAVE")
      (libsource (lib "eagle-import") (part "MLCC0603"))
    )
    (comp (ref "C103")
      (value "100n")
      (footprint "eagle-import:0603_WAVE")
      (libsource (lib "eagle-import") (part "MLCC0603"))
    )
    (comp (ref "C104")
      (value "100n")
      (footprint "eagle-import:0603_WAVE")
      (libsource (lib "eagle-import") (part "MLCC0603"))
    )
    (comp (ref "C105")
      (value "100n")
      (footprint "eagle-import:0603_WAVE")
      (libsource (lib "eagle-import") (part "MLCC0603"))
    )
    (comp (ref "C106")
      (value "100n")
      (footprint "eagle-import:0603_WAVE")
      (libsource (lib "eagle-import") (part "MLCC0603"))
    )
    (comp (ref "C107")
      (value "100n")
      (footprint "eagle-import:0603_WAVE")
      (libsource (lib "eagle-import") (part "MLCC0603"))
    )
    (comp (ref "C108")
      (value "100n")
      (footprint "eagle-import:0603_WAVE")
      (libsource (lib "eagle-import") (part "MLCC0603"))
    )
    (comp (ref "C109")
      (value "100n")
      (footprint "eagle-import:0603_WAVE")
      (libsource (lib "eagle-import") (part "MLCC0603"))
    )
    (comp (ref "C110")
      (value "100n")
      (footprint "eagle-import:0603_WAVE")
      (libsource (lib "eagle-import") (part "MLCC0603"))
    )
    (comp (ref "C111")
      (value "4u7")
      (footprint "eagle-import:0603_WAVE")
      (libsource (lib "eagle-import") (part "MLCC0603"))
    )
    (comp (ref "C112")
      (value "100n")
      (footprint "eagle-import:0603_WAVE")
      (libsource (lib "eagle-import") (part "MLCC0603"))
    )
    (comp (ref "C113")
      (value "4u7")
      (footprint "eagle-import:0603_WAVE")
      (libsource (lib "eagle-import") (part "MLCC0603"))
    )
    (comp (ref "C114")
      (value "100p")
      (footprint "eagle-import:0603_WAVE")
      (libsource (lib "eagle-import") (part "MLCC0603"))
    )
    (comp (ref "C115")
      (value "100p")
      (footprint "eagle-import:0603_WAVE")
      (libsource (lib "eagle-import") (part "MLCC0603"))
    )
    (comp (ref "C116")
      (value "100p")
      (footprint "eagle-import:0603_WAVE")
      (libsource (lib "eagle-import") (part "MLCC0603"))
    )
    (comp (ref "C117")
      (value "100p")
      (footprint "eagle-import:0603_WAVE")
      (libsource (lib "eagle-import") (part "MLCC0603"))
    )
    (comp (ref "C118")
      (value "100p")
      (footprint "eagle-import:0603_WAVE")
      (libsource (lib "eagle-import") (part "MLCC0603"))
    )
    (comp (ref "D101")
      (value "BAT54S")
      (footprint "eagle-import:SOT-23-3")
      (libsource (lib "eagle-import") (part "BAT54S"))
    )
    (comp (ref "R101")
      (value "10k")
      (footprint "eagle-import:0603_WAVE")
      (libsource (lib "eagle-import") (part "RESISTOR0603"))
    )
    (comp (ref "R102")
      (value "10k")
      (footprint "eagle-import:0603_WAVE")
      (libsource (lib "eagle-import") (part "RESISTOR0603"))
    )
    (comp (ref "R103")
      (value "10k")
      (footprint "eagle-import:0603_WAVE")
      (libsource (lib "eagle-import") (part "RESISTOR0603"))
    )
    (comp (ref "R104")
      (value "10k")
      (footprint "eagle-import:0603_WAVE")
      (libsource (lib "eagle-import") (part "RESISTOR0603"))
    )
    (comp (ref "R105")
      (value "10k")
      (footprint "eagle-import:0603_WAVE")
      (libsource (lib "eagle-import") (part "RESISTOR0603"))
    )
    (comp (ref "R106")
      (value "10k")
      (footprint "eagle-import:0603_WAVE")
      (libsource (lib "eagle-import") (part "RESISTOR0603"))
    )
    (comp (ref "R107")
      (value "10k")
      (footprint "eagle-import:0603_WAVE")
      (libsource (lib "eagle-import") (part "RESISTOR0603"))
    )
    (comp (ref "R108")
      (value "10k")
      (footprint "eagle-import:0603_WAVE")
      (libsource (lib "eagle-import") (part "RESISTOR0603"))
    )
    (comp (ref "R109")
      (value "10k")
      (footprint "eagle-import:0603_WAVE")
      (libsource (lib "eagle-import") (part "RESISTOR0603"))
    )
    (comp (ref "R110")
      (value "10k")
      (footprint "eagle-import:0603_WAVE")
      (libsource (lib "eagle-import") (part "RESISTOR0603"))
    )
    (comp (ref "R111")
      (value "100")
      (footprint "eagle-import:0603_WAVE")
      (libsource (lib "eagle-import") (part "RESISTOR0603"))
    )
    (comp (ref "R112")
      (value "100")
      (footprint "eagle-import:0603_WAVE")
      (libsource (lib "eagle-import") (part "RESISTOR0603"))
    )
    (comp (ref "R113")
      (value "100")
      (footprint "eagle-import:0603_WAVE")
      (libsource (lib "eagle-import") (part "RESISTOR0603"))
    )
    (comp (ref "R114")
      (value "10k")
      (footprint "eagle-import:0603_WAVE")
      (libsource (lib "eagle-import") (part "RESISTOR0603"))
    )
    (comp (ref "R115")
      (value "100")
      (footprint "eagle-import:0603_WAVE")
      (libsource (lib "eagle-import") (part "RESISTOR0603"))
    )
    (comp (ref "R116")
      (value "10k")
      (footprint "eagle-import:0603_WAVE")
      (libsource (lib "eagle-import") (part "RESISTOR0603"))
    )
    (comp (ref "R117")
      (value "10k")
      (footprint "eagle-import:0603_WAVE")
      (libsource (lib "eagle-import") (part "RESISTOR0603"))
    )
    (comp (ref "R118")
      (value "10k")
      (footprint "eagle-import:0603_WAVE")
      (libsource (lib "eagle-import") (part "RESISTOR0603"))
    )
    (comp (ref "R119")
      (value "140k")
      (footprint "eagle-import:0603_WAVE")
      (libsource (lib "eagle-import") (part "RESISTOR0603"))
    )
    (comp (ref "R120")
      (value "10k")
      (footprint "eagle-import:0603_WAVE")
      (libsource (lib "eagle-import") (part "RESISTOR0603"))
    )
    (comp (ref "R121")
      (value "10k")
      (footprint "eagle-import:0603_WAVE")
      (libsource (lib "eagle-import") (part "RESISTOR0603"))
    )
    (comp (ref "U101")
      (value "DSC1101")
      (footprint "eagle-import:CDFN_5X3.2")
      (libsource (lib "eagle-import") (part "DSC1101"))
    )
    (comp (ref "U102")
      (value "TMC4671")
      (footprint "eagle-import:QFN76")
      (libsource (lib "eagle-import") (part "TMC4671"))
    )
  )
  (nets
    (net (code "1") (name "1.8V") (class "Default")
      (node (ref "C103") (pin "P$1") (pinfunction "P$1_P$1") (pintype "bidirectional"))
      (node (ref "C105") (pin "P$1") (pinfunction "P$1_P$1") (pintype "bidirectional"))
      (node (ref "C107") (pin "P$1") (pinfunction "P$1_P$1") (pintype "bidirectional"))
      (node (ref "U102") (pin "15") (pinfunction "VCC_CORE_15") (pintype "bidirectional"))
      (node (ref "U102") (pin "45") (pinfunction "VCC_CORE_45") (pintype "bidirectional"))
      (node (ref "U102") (pin "63") (pinfunction "VCC_CORE_63") (pintype "bidirectional"))
    )
    (net (code "2") (name "3.3V") (class "Default")
      (node (ref "C101") (pin "P$1") (pinfunction "P$1_P$1") (pintype "bidirectional"))
      (node (ref "C102") (pin "P$1") (pinfunction "P$1_P$1") (pintype "bidirectional"))
      (node (ref "C104") (pin "P$1") (pinfunction "P$1_P$1") (pintype "bidirectional"))
      (node (ref "C106") (pin "P$1") (pinfunction "P$1_P$1") (pintype "bidirectional"))
      (node (ref "C108") (pin "P$1") (pinfunction "P$1_P$1") (pintype "bidirectional"))
      (node (ref "C109") (pin "P$1") (pinfunction "P$1_P$1") (pintype "bidirectional"))
      (node (ref "C110") (pin "P$1") (pinfunction "P$1_P$1") (pintype "bidirectional"))
      (node (ref "C111") (pin "P$1") (pinfunction "P$1_P$1") (pintype "bidirectional"))
      (node (ref "C214") (pin "P$1") (pinfunction "P$1_P$1") (pintype "bidirectional"))
      (node (ref "C215") (pin "P$1") (pinfunction "P$1_P$1") (pintype "bidirectional"))
      (node (ref "C216") (pin "P$1") (pinfunction "P$1_P$1") (pintype "bidirectional"))
      (node (ref "C217") (pin "P$1") (pinfunction "P$1_P$1") (pintype "bidirectional"))
      (node (ref "C309") (pin "P$1") (pinfunction "P$1_P$1") (pintype "bidirectional"))
      (node (ref "C405") (pin "P$1") (pinfunction "P$1_P$1") (pintype "bidirectional"))
      (node (ref "C407") (pin "P$1") (pinfunction "P$1_P$1") (pintype "bidirectional"))
      (node (ref "C409") (pin "P$1") (pinfunction "P$1_P$1") (pintype "bidirectional"))
      (node (ref "C411") (pin "P$1") (pinfunction "P$1_P$1") (pintype "bidirectional"))
      (node (ref "C413") (pin "P$1") (pinfunction "P$1_P$1") (pintype "bidirectional"))
      (node (ref "C414") (pin "P$1") (pinfunction "P$1_P$1") (pintype "bidirectional"))
      (node (ref "C415") (pin "P$1") (pinfunction "P$1_P$1") (pintype "bidirectional"))
      (node (ref "C416") (pin "P$1") (pinfunction "P$1_P$1") (pintype "bidirectional"))
      (node (ref "C501") (pin "P$1") (pinfunction "P$1_P$1") (pintype "bidirectional"))
      (node (ref "C502") (pin "P$1") (pinfunction "P$1_P$1") (pintype "bidirectional"))
      (node (ref "D504") (pin "P$2") (pinfunction "2_P$2") (pintype "bidirectional"))
      (node (ref "D505") (pin "P$2") (pinfunction "2_P$2") (pintype "bidirectional"))
      (node (ref "D506") (pin "P$2") (pinfunction "2_P$2") (pintype "bidirectional"))
      (node (ref "J505") (pin "1") (pinfunction "S_1") (pintype "passive"))
      (node (ref "R101") (pin "P$2") (pinfunction "P$2_P$2") (pintype "bidirectional"))
      (node (ref "R102") (pin "P$1") (pinfunction "P$1_P$1") (pintype "bidirectional"))
      (node (ref "R501") (pin "P$1") (pinfunction "P$1_P$1") (pintype "bidirectional"))
      (node (ref "R502") (pin "P$2") (pinfunction "P$2_P$2") (pintype "bidirectional"))
      (node (ref "R503") (pin "P$2") (pinfunction "P$2_P$2") (pintype "bidirectional"))
      (node (ref "U101") (pin "6") (pinfunction "VDD_6") (pintype "bidirectional"))
      (node (ref "U102") (pin "13") (pinfunction "VCC_13") (pintype "bidirectional"))
      (node (ref "U102") (pin "2") (pinfunction "VCC_2") (pintype "bidirectional"))
      (node (ref "U102") (pin "43") (pinfunction "VCC_43") (pintype "bidirectional"))
      (node (ref "U102") (pin "52") (pinfunction "PLL_VCC_52") (pintype "bidirectional"))
      (node (ref "U102") (pin "55") (pinfunction "ENI_55") (pintype "bidirectional"))
      (node (ref "U102") (pin "61") (pinfunction "VCC_61") (pintype "bidirectional"))
      (node (ref "U102") (pin "72") (pinfunction "VCC_72") (pintype "bidirectional"))
      (node (ref "U205") (pin "8") (pinfunction "VCC_8") (pintype "bidirectional"))
      (node (ref "U206") (pin "8") (pinfunction "VCC_8") (pintype "bidirectional"))
      (node (ref "U207") (pin "8") (pinfunction "VCC_8") (pintype "bidirectional"))
      (node (ref "U208") (pin "8") (pinfunction "VCC_8") (pintype "bidirectional"))
      (node (ref "U302") (pin "3") (pinfunction "VOUT_3") (pintype "bidirectional"))
      (node (ref "U401") (pin "3") (pinfunction "VDDI_3") (pintype "bidirectional"))
      (node (ref "U401") (pin "8") (pinfunction "VDDI_8") (pintype "bidirectional"))
      (node (ref "U402") (pin "3") (pinfunction "VDDI_3") (pintype "bidirectional"))
      (node (ref "U402") (pin "8") (pinfunction "VDDI_8") (pintype "bidirectional"))
      (node (ref "U403") (pin "3") (pinfunction "VDDI_3") (pintype "bidirectional"))
      (node (ref "U403") (pin "8") (pinfunction "VDDI_8") (pintype "bidirectional"))
      (node (ref "U404") (pin "3") (pinfunction "VDDI_3") (pintype "bidirectional"))
      (node (ref "U404") (pin "8") (pinfunction "VDDI_8") (pintype "bidirectional"))
      (node (ref "U501") (pin "5") (pinfunction "VIO_5") (pintype "bidirectional"))
      (node (ref "U501") (pin "6") (pinfunction "VDD_6") (pintype "bidirectional"))
      (node (ref "U501") (pin "7") (pinfunction "VREGIN_7") (pintype "bidirectional"))
    )
    (net (code "3") (name "5V") (class "Default")
      (node (ref "C112") (pin "P$1") (pinfunction "P$1_P$1") (pintype "bidirectional"))
      (node (ref "C113") (pin "P$1") (pinfunction "P$1_P$1") (pintype "bidirectional"))
      (node (ref "C201") (pin "P$1") (pinfunction "P$1_P$1") (pintype "bidirectional"))
      (node (ref "C202") (pin "P$1") (pinfunction "P$1_P$1") (pintype "bidirectional"))
      (node (ref "C203") (pin "P$1") (pinfunction "P$1_P$1") (pintype "bidirectional"))
      (node (ref "C204") (pin "P$1") (pinfunction "P$1_P$1") (pintype "bidirectional"))
      (node (ref "C205") (pin "P$1") (pinfunction "P$1_P$1") (pintype "bidirectional"))
      (node (ref "C222") (pin "P$1") (pinfunction "P$1_P$1") (pintype "bidirectional"))
      (node (ref "C223") (pin "P$1") (pinfunction "P$1_P$1") (pintype "bidirectional"))
      (node (ref "C224") (pin "P$1") (pinfunction "P$1_P$1") (pintype "bidirectional"))
      (node (ref "C225") (pin "P$1") (pinfunction "P$1_P$1") (pintype "bidirectional"))
      (node (ref "C310") (pin "P$1") (pinfunction "P$1_P$1") (pintype "bidirectional"))
      (node (ref "C422") (pin "P$1") (pinfunction "P$1_P$1") (pintype "bidirectional"))
      (node (ref "C423") (pin "P$1") (pinfunction "P$1_P$1") (pintype "bidirectional"))
      (node (ref "D101") (pin "P$2") (pinfunction "2_P$2") (pintype "bidirectional"))
      (node (ref "D201") (pin "P$2") (pinfunction "2_P$2") (pintype "bidirectional"))
      (node (ref "D202") (pin "P$2") (pinfunction "2_P$2") (pintype "bidirectional"))
      (node (ref "D203") (pin "P$2") (pinfunction "2_P$2") (pintype "bidirectional"))
      (node (ref "J201") (pin "1") (pinfunction "S_1") (pintype "passive"))
      (node (ref "J202") (pin "1") (pinfunction "S_1") (pintype "passive"))
      (node (ref "J203") (pin "1") (pinfunction "S_1") (pintype "passive"))
      (node (ref "J204") (pin "1") (pinfunction "S_1") (pintype "passive"))
      (node (ref "J205") (pin "1") (pinfunction "S_1") (pintype "passive"))
      (node (ref "J402") (pin "1") (pinfunction "S_1") (pintype "passive"))
      (node (ref "R103") (pin "P$2") (pinfunction "P$2_P$2") (pintype "bidirectional"))
      (node (ref "R106") (pin "P$2") (pinfunction "P$2_P$2") (pintype "bidirectional"))
      (node (ref "R109") (pin "P$2") (pinfunction "P$2_P$2") (pintype "bidirectional"))
      (node (ref "R117") (pin "P$2") (pinfunction "P$2_P$2") (pintype "bidirectional"))
      (node (ref "R120") (pin "P$2") (pinfunction "P$2_P$2") (pintype "bidirectional"))
      (node (ref "R214") (pin "P$1") (pinfunction "P$1_P$1") (pintype "bidirectional"))
      (node (ref "R215") (pin "P$1") (pinfunction "P$1_P$1") (pintype "bidirectional"))
      (node (ref "R216") (pin "P$1") (pinfunction "P$1_P$1") (pintype "bidirectional"))
      (node (ref "R217") (pin "P$1") (pinfunction "P$1_P$1") (pintype "bidirectional"))
      (node (ref "R219") (pin "P$1") (pinfunction "P$1_P$1") (pintype "bidirectional"))
      (node (ref "R220") (pin "P$1") (pinfunction "P$1_P$1") (pintype "bidirectional"))
      (node (ref "R221") (pin "P$1") (pinfunction "P$1_P$1") (pintype "bidirectional"))
      (node (ref "R222") (pin "P$1") (pinfunction "P$1_P$1") (pintype "bidirectional"))
      (node (ref "R223") (pin "P$1") (pinfunction "P$1_P$1") (pintype "bidirectional"))
      (node (ref "R224") (pin "P$1") (pinfunction "P$1_P$1") (pintype "bidirectional"))
      (node (ref "R225") (pin "P$1") (pinfunction "P$1_P$1") (pintype "bidirectional"))
      (node (ref "R226") (pin "P$1") (pinfunction "P$1_P$1") (pintype "bidirectional"))
      (node (ref "R427") (pin "P$2") (pinfunction "P$2_P$2") (pintype "bidirectional"))
      (node (ref "U102") (pin "23") (pinfunction "V5_23") (pintype "bidirectional"))
      (node (ref "U201") (pin "5") (pinfunction "VCC_5") (pintype "bidirectional"))
      (node (ref "U202") (pin "5") (pinfunction "VCC_5") (pintype "bidirectional"))
      (node (ref "U203") (pin "5") (pinfunction "VCC_5") (pintype "bidirectional"))
      (node (ref "U204") (pin "5") (pinfunction "VCC_5") (pintype "bidirectional"))
      (node (ref "U303") (pin "3") (pinfunction "VOUT_3") (pintype "bidirectional"))
      (node (ref "U405") (pin "6") (pinfunction "P$1_6") (pintype "bidirectional"))
      (node (ref "U405") (pin "7") (pinfunction "P$1_7") (pintype "bidirectional"))
      (node (ref "U406") (pin "6") (pinfunction "P$1_6") (pintype "bidirectional"))
      (node (ref "U406") (pin "7") (pinfunction "P$1_7") (pintype "bidirectional"))
    )
    (net (code "4") (name "12V") (class "Default")
      (node (ref "C301") (pin "P$1") (pinfunction "P$1_P$1") (pintype "bidirectional"))
      (node (ref "C302") (pin "+") (pinfunction "AN_+") (pintype "bidirectional"))
      (node (ref "C401") (pin "P$1") (pinfunction "P$1_P$1") (pintype "bidirectional"))
      (node (ref "C402") (pin "P$1") (pinfunction "P$1_P$1") (pintype "bidirectional"))
      (node (ref "C403") (pin "P$1") (pinfunction "P$1_P$1") (pintype "bidirectional"))
      (node (ref "C404") (pin "P$1") (pinfunction "P$1_P$1") (pintype "bidirectional"))
      (node (ref "C406") (pin "P$1") (pinfunction "P$1_P$1") (pintype "bidirectional"))
      (node (ref "C408") (pin "P$1") (pinfunction "P$1_P$1") (pintype "bidirectional"))
      (node (ref "C410") (pin "P$1") (pinfunction "P$1_P$1") (pintype "bidirectional"))
      (node (ref "C412") (pin "P$1") (pinfunction "P$1_P$1") (pintype "bidirectional"))
      (node (ref "C421") (pin "P$1") (pinfunction "P$1_P$1") (pintype "bidirectional"))
      (node (ref "C424") (pin "P$1") (pinfunction "P$1_P$1") (pintype "bidirectional"))
      (node (ref "J301") (pin "2") (pinfunction "S_2") (pintype "passive"))
      (node (ref "R301") (pin "P$2") (pinfunction "P$2_P$2") (pintype "bidirectional"))
      (node (ref "R409") (pin "P$1") (pinfunction "P$1_P$1") (pintype "bidirectional"))
      (node (ref "R410") (pin "P$1") (pinfunction "P$1_P$1") (pintype "bidirectional"))
      (node (ref "R411") (pin "P$1") (pinfunction "P$1_P$1") (pintype "bidirectional"))
      (node (ref "R412") (pin "P$1") (pinfunction "P$1_P$1") (pintype "bidirectional"))
      (node (ref "U301") (pin "5") (pinfunction "IN_5") (pintype "bidirectional"))
      (node (ref "U401") (pin "11") (pinfunction "VDDB_11") (pintype "bidirectional"))
      (node (ref "U402") (pin "11") (pinfunction "VDDB_11") (pintype "bidirectional"))
      (node (ref "U403") (pin "11") (pinfunction "VDDB_11") (pintype "bidirectional"))
      (node (ref "U404") (pin "11") (pinfunction "VDDB_11") (pintype "bidirectional"))
      (node (ref "U407") (pin "8") (pinfunction "VDD_8") (pintype "bidirectional"))
    )
    (net (code "5") (name "ADC_I0_U_PF") (class "Default")
      (node (ref "R113") (pin "P$2") (pinfunction "P$2_P$2") (pintype "bidirectional"))
      (node (ref "U405") (pin "5") (pinfunction "O_5") (pintype "bidirectional"))
    )
    (net (code "6") (name "ADC_I1_V_PF") (class "Default")
      (node (ref "R115") (pin "P$2") (pinfunction "P$2_P$2") (pintype "bidirectional"))
      (node (ref "U406") (pin "5") (pinfunction "O_5") (pintype "bidirectional"))
    )
    (net (code "7") (name "ADC_T_MOSFETS") (class "Default")
      (node (ref "C425") (pin "P$1") (pinfunction "P$1_P$1") (pintype "bidirectional"))
      (node (ref "R111") (pin "P$2") (pinfunction "P$2_P$2") (pintype "bidirectional"))
      (node (ref "R427") (pin "P$1") (pinfunction "P$1_P$1") (pintype "bidirectional"))
      (node (ref "R428") (pin "P$2") (pinfunction "P$2_P$2") (pintype "bidirectional"))
    )
    (net (code "8") (name "ADC_T_MOTOR") (class "Default")
      (node (ref "C432") (pin "P$1") (pinfunction "P$1_P$1") (pintype "bidirectional"))
      (node (ref "J402") (pin "2") (pinfunction "S_2") (pintype "passive"))
      (node (ref "R112") (pin "P$1") (pinfunction "P$1_P$1") (pintype "bidirectional"))
      (node (ref "R430") (pin "P$2") (pinfunction "P$2_P$2") (pintype "bidirectional"))
    )
    (net (code "9") (name "AENC_UX_P") (class "Default")
      (node (ref "C226") (pin "P$1") (pinfunction "P$1_P$1") (pintype "bidirectional"))
      (node (ref "D201") (pin "P$3") (pinfunction "3_P$3") (pintype "bidirectional"))
      (node (ref "R213") (pin "P$2") (pinfunction "P$2_P$2") (pintype "bidirectional"))
      (node (ref "U102") (pin "25") (pinfunction "AENC_UX_POS_25") (pintype "bidirectional"))
    )
    (net (code "10") (name "AENC_VN_P") (class "Default")
      (node (ref "C227") (pin "P$1") (pinfunction "P$1_P$1") (pintype "bidirectional"))
      (node (ref "D202") (pin "P$3") (pinfunction "3_P$3") (pintype "bidirectional"))
      (node (ref "R218") (pin "P$2") (pinfunction "P$2_P$2") (pintype "bidirectional"))
      (node (ref "U102") (pin "27") (pinfunction "AENC_VN_POS_27") (pintype "bidirectional"))
    )
    (net (code "11") (name "AENC_WY_P") (class "Default")
      (node (ref "C228") (pin "P$1") (pinfunction "P$1_P$1") (pintype "bidirectional"))
      (node (ref "D203") (pin "P$3") (pinfunction "3_P$3") (pintype "bidirectional"))
      (node (ref "R227") (pin "P$2") (pinfunction "P$2_P$2") (pintype "bidirectional"))
      (node (ref "U102") (pin "29") (pinfunction "AENC_WY_POS_29") (pintype "bidirectional"))
    )
    (net (code "12") (name "BRAKE") (class "Default")
      (node (ref "R429") (pin "P$2") (pinfunction "P$2_P$2") (pintype "bidirectional"))
      (node (ref "U102") (pin "31") (pinfunction "BRAKE_31") (pintype "bidirectional"))
    )
    (net (code "13") (name "CP2102_RX") (class "Default")
      (node (ref "J502") (pin "2") (pinfunction "S_2") (pintype "passive"))
      (node (ref "JP505") (pin "2") (pinfunction "2_2") (pintype "passive"))
      (node (ref "U102") (pin "11") (pinfunction "TXD_SYNCO_11") (pintype "bidirectional"))
    )
    (net (code "14") (name "CP2102_TX") (class "Default")
      (node (ref "J502") (pin "1") (pinfunction "S_1") (pintype "passive"))
      (node (ref "JP506") (pin "2") (pinfunction "2_2") (pintype "passive"))
      (node (ref "U102") (pin "10") (pinfunction "RXD_SYNCI_10") (pintype "bidirectional"))
    )
    (net (code "15") (name "D+") (class "Default")
      (node (ref "D503") (pin "3") (pinfunction "3_3") (pintype "bidirectional"))
      (node (ref "J503") (pin "D+") (pinfunction "D+_D+") (pintype "bidirectional"))
      (node (ref "U501") (pin "3") (pinfunction "D+_3") (pintype "bidirectional"))
    )
    (net (code "16") (name "D-") (class "Default")
      (node (ref "D503") (pin "2") (pinfunction "2_2") (pintype "bidirectional"))
      (node (ref "J503") (pin "D-") (pinfunction "D-_D-") (pintype "bidirectional"))
      (node (ref "U501") (pin "4") (pinfunction "D-_4") (pintype "bidirectional"))
    )
    (net (code "17") (name "DBG_SPI_MISO") (class "Default")
      (node (ref "J505") (pin "9") (pinfunction "S_9") (pintype "passive"))
      (node (ref "U102") (pin "4") (pinfunction "GPIO6_4") (pintype "bidirectional"))
    )
    (net (code "18") (name "DBG_SPI_MOSI") (class "Default")
      (node (ref "J505") (pin "7") (pinfunction "S_7") (pintype "passive"))
      (node (ref "U102") (pin "1") (pinfunction "GPIO5_1") (pintype "bidirectional"))
    )
    (net (code "19") (name "DBG_SPI_NSCS") (class "Default")
      (node (ref "J505") (pin "3") (pinfunction "S_3") (pintype "passive"))
      (node (ref "U102") (pin "75") (pinfunction "GPIO3_75") (pintype "bidirectional"))
    )
    (net (code "20") (name "DBG_SPI_SCK") (class "Default")
      (node (ref "J505") (pin "5") (pinfunction "S_5") (pintype "passive"))
      (node (ref "U102") (pin "76") (pinfunction "GPIO4_76") (pintype "bidirectional"))
    )
    (net (code "21") (name "DBG_SPI_TRG") (class "Default")
      (node (ref "J505") (pin "4") (pinfunction "S_4") (pintype "passive"))
      (node (ref "U102") (pin "5") (pinfunction "GPIO7_5") (pintype "bidirectional"))
    )
    (net (code "22") (name "DCBUS") (class "Default")
      (node (ref "C303") (pin "+") (pinfunction "AN_+") (pintype "bidirectional"))
      (node (ref "C304") (pin "+") (pinfunction "AN_+") (pintype "bidirectional"))
      (node (ref "C306") (pin "+") (pinfunction "AN_+") (pintype "bidirectional"))
      (node (ref "C308") (pin "+") (pinfunction "AN_+") (pintype "bidirectional"))
      (node (ref "J302") (pin "1") (pinfunction "S_1") (pintype "passive"))
      (node (ref "J403") (pin "1") (pinfunction "S_1") (pintype "passive"))
      (node (ref "P301") (pin "H1") (pinfunction "S_H1") (pintype "passive"))
      (node (ref "P301") (pin "H10") (pinfunction "S_H10") (pintype "passive"))
      (node (ref "P301") (pin "H11") (pinfunction "S_H11") (pintype "passive"))
      (node (ref "P301") (pin "H12") (pinfunction "S_H12") (pintype "passive"))
      (node (ref "P301") (pin "H2") (pinfunction "S_H2") (pintype "passive"))
      (node (ref "P301") (pin "H3") (pinfunction "S_H3") (pintype "passive"))
      (node (ref "P301") (pin "H4") (pinfunction "S_H4") (pintype "passive"))
      (node (ref "P301") (pin "H5") (pinfunction "S_H5") (pintype "passive"))
      (node (ref "P301") (pin "H6") (pinfunction "S_H6") (pintype "passive"))
      (node (ref "P301") (pin "H7") (pinfunction "S_H7") (pintype "passive"))
      (node (ref "P301") (pin "H8") (pinfunction "S_H8") (pintype "passive"))
      (node (ref "P301") (pin "H9") (pinfunction "S_H9") (pintype "passive"))
      (node (ref "P301") (pin "PAD") (pinfunction "S_PAD") (pintype "passive"))
      (node (ref "P405") (pin "H1") (pinfunction "S_H1") (pintype "passive"))
      (node (ref "P405") (pin "H10") (pinfunction "S_H10") (pintype "passive"))
      (node (ref "P405") (pin "H11") (pinfunction "S_H11") (pintype "passive"))
      (node (ref "P405") (pin "H12") (pinfunction "S_H12") (pintype "passive"))
      (node (ref "P405") (pin "H2") (pinfunction "S_H2") (pintype "passive"))
      (node (ref "P405") (pin "H3") (pinfunction "S_H3") (pintype "passive"))
      (node (ref "P405") (pin "H4") (pinfunction "S_H4") (pintype "passive"))
      (node (ref "P405") (pin "H5") (pinfunction "S_H5") (pintype "passive"))
      (node (ref "P405") (pin "H6") (pinfunction "S_H6") (pintype "passive"))
      (node (ref "P405") (pin "H7") (pinfunction "S_H7") (pintype "passive"))
      (node (ref "P405") (pin "H8") (pinfunction "S_H8") (pintype "passive"))
      (node (ref "P405") (pin "H9") (pinfunction "S_H9") (pintype "passive"))
      (node (ref "P405") (pin "PAD") (pinfunction "S_PAD") (pintype "passive"))
      (node (ref "Q401") (pin "D1") (pinfunction "D1_D1") (pintype "bidirectional"))
      (node (ref "Q401") (pin "D2") (pinfunction "D1_D2") (pintype "bidirectional"))
      (node (ref "Q401") (pin "D3") (pinfunction "D1_D3") (pintype "bidirectional"))
      (node (ref "Q401") (pin "D4") (pinfunction "D1_D4") (pintype "bidirectional"))
      (node (ref "Q402") (pin "D1") (pinfunction "D1_D1") (pintype "bidirectional"))
      (node (ref "Q402") (pin "D2") (pinfunction "D1_D2") (pintype "bidirectional"))
      (node (ref "Q402") (pin "D3") (pinfunction "D1_D3") (pintype "bidirectional"))
      (node (ref "Q402") (pin "D4") (pinfunction "D1_D4") (pintype "bidirectional"))
      (node (ref "Q403") (pin "D1") (pinfunction "D1_D1") (pintype "bidirectional"))
      (node (ref "Q403") (pin "D2") (pinfunction "D1_D2") (pintype "bidirectional"))
      (node (ref "Q403") (pin "D3") (pinfunction "D1_D3") (pintype "bidirectional"))
      (node (ref "Q403") (pin "D4") (pinfunction "D1_D4") (pintype "bidirectional"))
      (node (ref "Q404") (pin "D1") (pinfunction "D1_D1") (pintype "bidirectional"))
      (node (ref "Q404") (pin "D2") (pinfunction "D1_D2") (pintype "bidirectional"))
      (node (ref "Q404") (pin "D3") (pinfunction "D1_D3") (pintype "bidirectional"))
      (node (ref "Q404") (pin "D4") (pinfunction "D1_D4") (pintype "bidirectional"))
      (node (ref "R119") (pin "P$2") (pinfunction "P$2_P$2") (pintype "bidirectional"))
    )
    (net (code "23") (name "DIR") (class "Default")
      (node (ref "D505") (pin "P$3") (pinfunction "3_P$3") (pintype "bidirectional"))
      (node (ref "R508") (pin "P$2") (pinfunction "P$2_P$2") (pintype "bidirectional"))
      (node (ref "R511") (pin "P$2") (pinfunction "P$2_P$2") (pintype "bidirectional"))
      (node (ref "U102") (pin "56") (pinfunction "DIR_56") (pintype "bidirectional"))
    )
    (net (code "24") (name "ENC2_A") (class "Default")
      (node (ref "U102") (pin "64") (pinfunction "ENC2_A_64") (pintype "bidirectional"))
      (node (ref "U206") (pin "7") (pinfunction "Y_7") (pintype "output"))
    )
    (net (code "25") (name "ENC2_B") (class "Default")
      (node (ref "U102") (pin "65") (pinfunction "ENC2_B_65") (pintype "bidirectional"))
      (node (ref "U206") (pin "5") (pinfunction "Y_5") (pintype "output"))
    )
    (net (code "26") (name "ENC2_N") (class "Default")
      (node (ref "U102") (pin "66") (pinfunction "ENC2_N_66") (pintype "bidirectional"))
      (node (ref "U206") (pin "2") (pinfunction "Y_2") (pintype "output"))
    )
    (net (code "27") (name "ENC_A") (class "Default")
      (node (ref "U102") (pin "35") (pinfunction "ENC_A_35") (pintype "bidirectional"))
      (node (ref "U205") (pin "7") (pinfunction "Y_7") (pintype "output"))
    )
    (net (code "28") (name "ENC_B") (class "Default")
      (node (ref "U102") (pin "34") (pinfunction "ENC_B_34") (pintype "bidirectional"))
      (node (ref "U205") (pin "5") (pinfunction "Y_5") (pintype "output"))
    )
    (net (code "29") (name "ENC_N") (class "Default")
      (node (ref "U102") (pin "33") (pinfunction "ENC_N_33") (pintype "bidirectional"))
      (node (ref "U205") (pin "2") (pinfunction "Y_2") (pintype "output"))
    )
    (net (code "30") (name "ENO") (class "Default")
      (node (ref "R114") (pin "P$1") (pinfunction "P$1_P$1") (pintype "bidirectional"))
      (node (ref "U102") (pin "32") (pinfunction "ENO_32") (pintype "bidirectional"))
      (node (ref "U401") (pin "5") (pinfunction "EN_5") (pintype "bidirectional"))
      (node (ref "U402") (pin "5") (pinfunction "EN_5") (pintype "bidirectional"))
      (node (ref "U403") (pin "5") (pinfunction "EN_5") (pintype "bidirectional"))
      (node (ref "U404") (pin "5") (pinfunction "EN_5") (pintype "bidirectional"))
    )
    (net (code "31") (name "GND") (class "Default")
      (node (ref "C101") (pin "P$2") (pinfunction "P$2_P$2") (pintype "bidirectional"))
      (node (ref "C102") (pin "P$2") (pinfunction "P$2_P$2") (pintype "bidirectional"))
      (node (ref "C103") (pin "P$2") (pinfunction "P$2_P$2") (pintype "bidirectional"))
      (node (ref "C104") (pin "P$2") (pinfunction "P$2_P$2") (pintype "bidirectional"))
      (node (ref "C105") (pin "P$2") (pinfunction "P$2_P$2") (pintype "bidirectional"))
      (node (ref "C106") (pin "P$2") (pinfunction "P$2_P$2") (pintype "bidirectional"))
      (node (ref "C107") (pin "P$2") (pinfunction "P$2_P$2") (pintype "bidirectional"))
      (node (ref "C108") (pin "P$2") (pinfunction "P$2_P$2") (pintype "bidirectional"))
      (node (ref "C109") (pin "P$2") (pinfunction "P$2_P$2") (pintype "bidirectional"))
      (node (ref "C110") (pin "P$2") (pinfunction "P$2_P$2") (pintype "bidirectional"))
      (node (ref "C111") (pin "P$2") (pinfunction "P$2_P$2") (pintype "bidirectional"))
      (node (ref "C112") (pin "P$2") (pinfunction "P$2_P$2") (pintype "bidirectional"))
      (node (ref "C113") (pin "P$2") (pinfunction "P$2_P$2") (pintype "bidirectional"))
      (node (ref "C114") (pin "P$2") (pinfunction "P$2_P$2") (pintype "bidirectional"))
      (node (ref "C115") (pin "P$2") (pinfunction "P$2_P$2") (pintype "bidirectional"))
      (node (ref "C116") (pin "P$2") (pinfunction "P$2_P$2") (pintype "bidirectional"))
      (node (ref "C117") (pin "P$2") (pinfunction "P$2_P$2") (pintype "bidirectional"))
      (node (ref "C118") (pin "P$2") (pinfunction "P$2_P$2") (pintype "bidirectional"))
      (node (ref "C201") (pin "P$2") (pinfunction "P$2_P$2") (pintype "bidirectional"))
      (node (ref "C202") (pin "P$2") (pinfunction "P$2_P$2") (pintype "bidirectional"))
      (node (ref "C203") (pin "P$2") (pinfunction "P$2_P$2") (pintype "bidirectional"))
      (node (ref "C204") (pin "P$2") (pinfunction "P$2_P$2") (pintype "bidirectional"))
      (node (ref "C205") (pin "P$2") (pinfunction "P$2_P$2") (pintype "bidirectional"))
      (node (ref "C206") (pin "P$2") (pinfunction "P$2_P$2") (pintype "bidirectional"))
      (node (ref "C207") (pin "P$2") (pinfunction "P$2_P$2") (pintype "bidirectional"))
      (node (ref "C208") (pin "P$2") (pinfunction "P$2_P$2") (pintype "bidirectional"))
      (node (ref "C209") (pin "P$2") (pinfunction "P$2_P$2") (pintype "bidirectional"))
      (node (ref "C210") (pin "P$2") (pinfunction "P$2_P$2") (pintype "bidirectional"))
      (node (ref "C211") (pin "P$2") (pinfunction "P$2_P$2") (pintype "bidirectional"))
      (node (ref "C212") (pin "P$2") (pinfunction "P$2_P$2") (pintype "bidirectional"))
      (node (ref "C213") (pin "P$2") (pinfunction "P$2_P$2") (pintype "bidirectional"))
      (node (ref "C214") (pin "P$2") (pinfunction "P$2_P$2") (pintype "bidirectional"))
      (node (ref "C215") (pin "P$2") (pinfunction "P$2_P$2") (pintype "bidirectional"))
      (node (ref "C216") (pin "P$2") (pinfunction "P$2_P$2") (pintype "bidirectional"))
      (node (ref "C217") (pin "P$2") (pinfunction "P$2_P$2") (pintype "bidirectional"))
      (node (ref "C218") (pin "P$2") (pinfunction "P$2_P$2") (pintype "bidirectional"))
      (node (ref "C219") (pin "P$2") (pinfunction "P$2_P$2") (pintype "bidirectional"))
      (node (ref "C220") (pin "P$2") (pinfunction "P$2_P$2") (pintype "bidirectional"))
      (node (ref "C221") (pin "P$2") (pinfunction "P$2_P$2") (pintype "bidirectional"))
      (node (ref "C222") (pin "P$2") (pinfunction "P$2_P$2") (pintype "bidirectional"))
      (node (ref "C223") (pin "P$2") (pinfunction "P$2_P$2") (pintype "bidirectional"))
      (node (ref "C224") (pin "P$2") (pinfunction "P$2_P$2") (pintype "bidirectional"))
      (node (ref "C225") (pin "P$2") (pinfunction "P$2_P$2") (pintype "bidirectional"))
      (node (ref "C226") (pin "P$2") (pinfunction "P$2_P$2") (pintype "bidirectional"))
      (node (ref "C227") (pin "P$2") (pinfunction "P$2_P$2") (pintype "bidirectional"))
      (node (ref "C228") (pin "P$2") (pinfunction "P$2_P$2") (pintype "bidirectional"))
      (node (ref "C301") (pin "P$2") (pinfunction "P$2_P$2") (pintype "bidirectional"))
      (node (ref "C302") (pin "-") (pinfunction "CA_-") (pintype "bidirectional"))
      (node (ref "C303") (pin "-") (pinfunction "CA_-") (pintype "bidirectional"))
      (node (ref "C304") (pin "-") (pinfunction "CA_-") (pintype "bidirectional"))
      (node (ref "C305") (pin "P$2") (pinfunction "P$2_P$2") (pintype "bidirectional"))
      (node (ref "C306") (pin "-") (pinfunction "CA_-") (pintype "bidirectional"))
      (node (ref "C307") (pin "-") (pinfunction "CA_-") (pintype "bidirectional"))
      (node (ref "C308") (pin "-") (pinfunction "CA_-") (pintype "bidirectional"))
      (node (ref "C309") (pin "P$2") (pinfunction "P$2_P$2") (pintype "bidirectional"))
      (node (ref "C310") (pin "P$2") (pinfunction "P$2_P$2") (pintype "bidirectional"))
      (node (ref "C401") (pin "P$2") (pinfunction "P$2_P$2") (pintype "bidirectional"))
      (node (ref "C402") (pin "P$2") (pinfunction "P$2_P$2") (pintype "bidirectional"))
      (node (ref "C403") (pin "P$2") (pinfunction "P$2_P$2") (pintype "bidirectional"))
      (node (ref "C404") (pin "P$2") (pinfunction "P$2_P$2") (pintype "bidirectional"))
      (node (ref "C405") (pin "P$2") (pinfunction "P$2_P$2") (pintype "bidirectional"))
      (node (ref "C406") (pin "P$2") (pinfunction "P$2_P$2") (pintype "bidirectional"))
      (node (ref "C407") (pin "P$2") (pinfunction "P$2_P$2") (pintype "bidirectional"))
      (node (ref "C408") (pin "P$2") (pinfunction "P$2_P$2") (pintype "bidirectional"))
      (node (ref "C409") (pin "P$2") (pinfunction "P$2_P$2") (pintype "bidirectional"))
      (node (ref "C410") (pin "P$2") (pinfunction "P$2_P$2") (pintype "bidirectional"))
      (node (ref "C411") (pin "P$2") (pinfunction "P$2_P$2") (pintype "bidirectional"))
      (node (ref "C412") (pin "P$2") (pinfunction "P$2_P$2") (pintype "bidirectional"))
      (node (ref "C413") (pin "P$2") (pinfunction "P$2_P$2") (pintype "bidirectional"))
      (node (ref "C414") (pin "P$2") (pinfunction "P$2_P$2") (pintype "bidirectional"))
      (node (ref "C415") (pin "P$2") (pinfunction "P$2_P$2") (pintype "bidirectional"))
      (node (ref "C416") (pin "P$2") (pinfunction "P$2_P$2") (pintype "bidirectional"))
      (node (ref "C421") (pin "P$2") (pinfunction "P$2_P$2") (pintype "bidirectional"))
      (node (ref "C422") (pin "P$2") (pinfunction "P$2_P$2") (pintype "bidirectional"))
      (node (ref "C423") (pin "P$2") (pinfunction "P$2_P$2") (pintype "bidirectional"))
      (node (ref "C424") (pin "P$2") (pinfunction "P$2_P$2") (pintype "bidirectional"))
      (node (ref "C425") (pin "P$2") (pinfunction "P$2_P$2") (pintype "bidirectional"))
      (node (ref "C426") (pin "P$1") (pinfunction "P$1_P$1") (pintype "bidirectional"))
      (node (ref "C428") (pin "P$2") (pinfunction "P$2_P$2") (pintype "bidirectional"))
      (node (ref "C429") (pin "P$1") (pinfunction "P$1_P$1") (pintype "bidirectional"))
      (node (ref "C431") (pin "P$2") (pinfunction "P$2_P$2") (pintype "bidirectional"))
      (node (ref "C432") (pin "P$2") (pinfunction "P$2_P$2") (pintype "bidirectional"))
      (node (ref "C501") (pin "P$2") (pinfunction "P$2_P$2") (pintype "bidirectional"))
      (node (ref "C502") (pin "P$2") (pinfunction "P$2_P$2") (pintype "bidirectional"))
      (node (ref "C503") (pin "P$2") (pinfunction "P$2_P$2") (pintype "bidirectional"))
      (node (ref "D101") (pin "P$1") (pinfunction "1_P$1") (pintype "bidirectional"))
      (node (ref "D201") (pin "P$1") (pinfunction "1_P$1") (pintype "bidirectional"))
      (node (ref "D202") (pin "P$1") (pinfunction "1_P$1") (pintype "bidirectional"))
      (node (ref "D203") (pin "P$1") (pinfunction "1_P$1") (pintype "bidirectional"))
      (node (ref "D301") (pin "A") (pinfunction "A_A") (pintype "bidirectional"))
      (node (ref "D302") (pin "C") (pinfunction "CA_C") (pintype "bidirectional"))
      (node (ref "D503") (pin "1") (pinfunction "1_1") (pintype "bidirectional"))
      (node (ref "D504") (pin "P$1") (pinfunction "1_P$1") (pintype "bidirectional"))
      (node (ref "D505") (pin "P$1") (pinfunction "1_P$1") (pintype "bidirectional"))
      (node (ref "D506") (pin "P$1") (pinfunction "1_P$1") (pintype "bidirectional"))
      (node (ref "J201") (pin "5") (pinfunction "S_5") (pintype "passive"))
      (node (ref "J201") (pin "FIT@1") (pinfunction "S_FIT@1") (pintype "passive"))
      (node (ref "J201") (pin "FIT@2") (pinfunction "S_FIT@2") (pintype "passive"))
      (node (ref "J202") (pin "5") (pinfunction "S_5") (pintype "passive"))
      (node (ref "J202") (pin "FIT@1") (pinfunction "S_FIT@1") (pintype "passive"))
      (node (ref "J202") (pin "FIT@2") (pinfunction "S_FIT@2") (pintype "passive"))
      (node (ref "J203") (pin "5") (pinfunction "S_5") (pintype "passive"))
      (node (ref "J203") (pin "FIT@1") (pinfunction "S_FIT@1") (pintype "passive"))
      (node (ref "J203") (pin "FIT@2") (pinfunction "S_FIT@2") (pintype "passive"))
      (node (ref "J204") (pin "5") (pinfunction "S_5") (pintype "passive"))
      (node (ref "J204") (pin "FIT@1") (pinfunction "S_FIT@1") (pintype "passive"))
      (node (ref "J204") (pin "FIT@2") (pinfunction "S_FIT@2") (pintype "passive"))
      (node (ref "J205") (pin "5") (pinfunction "S_5") (pintype "passive"))
      (node (ref "J205") (pin "FIT@1") (pinfunction "S_FIT@1") (pintype "passive"))
      (node (ref "J205") (pin "FIT@2") (pinfunction "S_FIT@2") (pintype "passive"))
      (node (ref "J301") (pin "1") (pinfunction "S_1") (pintype "passive"))
      (node (ref "J302") (pin "2") (pinfunction "S_2") (pintype "passive"))
      (node (ref "J402") (pin "FIT@1") (pinfunction "S_FIT@1") (pintype "passive"))
      (node (ref "J402") (pin "FIT@2") (pinfunction "S_FIT@2") (pintype "passive"))
      (node (ref "J501") (pin "6") (pinfunction "S_6") (pintype "passive"))
      (node (ref "J501") (pin "FIT@1") (pinfunction "S_FIT@1") (pintype "passive"))
      (node (ref "J501") (pin "FIT@2") (pinfunction "S_FIT@2") (pintype "passive"))
      (node (ref "J502") (pin "3") (pinfunction "S_3") (pintype "passive"))
      (node (ref "J502") (pin "FIT@1") (pinfunction "S_FIT@1") (pintype "passive"))
      (node (ref "J502") (pin "FIT@2") (pinfunction "S_FIT@2") (pintype "passive"))
      (node (ref "J503") (pin "GND") (pinfunction "GND_GND") (pintype "bidirectional"))
      (node (ref "J503") (pin "GND@1") (pinfunction "CASE_GND@1") (pintype "bidirectional"))
      (node (ref "J503") (pin "GND@2") (pinfunction "CASE_GND@2") (pintype "bidirectional"))
      (node (ref "J503") (pin "GND@3") (pinfunction "CASE_GND@3") (pintype "bidirectional"))
      (node (ref "J503") (pin "GND@4") (pinfunction "CASE_GND@4") (pintype "bidirectional"))
      (node (ref "J504") (pin "2") (pinfunction "S_2") (pintype "passive"))
      (node (ref "J504") (pin "FIT@1") (pinfunction "S_FIT@1") (pintype "passive"))
      (node (ref "J504") (pin "FIT@2") (pinfunction "S_FIT@2") (pintype "passive"))
      (node (ref "J505") (pin "10") (pinfunction "S_10") (pintype "passive"))
      (node (ref "J505") (pin "6") (pinfunction "S_6") (pintype "passive"))
      (node (ref "J505") (pin "8") (pinfunction "S_8") (pintype "passive"))
      (node (ref "J505") (pin "TAB1") (pinfunction "S_TAB1") (pintype "passive"))
      (node (ref "J505") (pin "TAB2") (pinfunction "S_TAB2") (pintype "passive"))
      (node (ref "J506") (pin "3") (pinfunction "S_3") (pintype "passive"))
      (node (ref "J506") (pin "FIT@1") (pinfunction "S_FIT@1") (pintype "passive"))
      (node (ref "J506") (pin "FIT@2") (pinfunction "S_FIT@2") (pintype "passive"))
      (node (ref "P302") (pin "H1") (pinfunction "S_H1") (pintype "passive"))
      (node (ref "P302") (pin "H10") (pinfunction "S_H10") (pintype "passive"))
      (node (ref "P302") (pin "H11") (pinfunction "S_H11") (pintype "passive"))
      (node (ref "P302") (pin "H12") (pinfunction "S_H12") (pintype "passive"))
      (node (ref "P302") (pin "H2") (pinfunction "S_H2") (pintype "passive"))
      (node (ref "P302") (pin "H3") (pinfunction "S_H3") (pintype "passive"))
      (node (ref "P302") (pin "H4") (pinfunction "S_H4") (pintype "passive"))
      (node (ref "P302") (pin "H5") (pinfunction "S_H5") (pintype "passive"))
      (node (ref "P302") (pin "H6") (pinfunction "S_H6") (pintype "passive"))
      (node (ref "P302") (pin "H7") (pinfunction "S_H7") (pintype "passive"))
      (node (ref "P302") (pin "H8") (pinfunction "S_H8") (pintype "passive"))
      (node (ref "P302") (pin "H9") (pinfunction "S_H9") (pintype "passive"))
      (node (ref "P302") (pin "PAD") (pinfunction "S_PAD") (pintype "passive"))
      (node (ref "Q405") (pin "S1") (pinfunction "S1_S1") (pintype "bidirectional"))
      (node (ref "Q405") (pin "S2") (pinfunction "S1_S2") (pintype "bidirectional"))
      (node (ref "Q405") (pin "S3") (pinfunction "S1_S3") (pintype "bidirectional"))
      (node (ref "Q405") (pin "S4") (pinfunction "S1_S4") (pintype "bidirectional"))
      (node (ref "Q405") (pin "S5") (pinfunction "S1_S5") (pintype "bidirectional"))
      (node (ref "Q406") (pin "S1") (pinfunction "S1_S1") (pintype "bidirectional"))
      (node (ref "Q406") (pin "S2") (pinfunction "S1_S2") (pintype "bidirectional"))
      (node (ref "Q406") (pin "S3") (pinfunction "S1_S3") (pintype "bidirectional"))
      (node (ref "Q406") (pin "S4") (pinfunction "S1_S4") (pintype "bidirectional"))
      (node (ref "Q406") (pin "S5") (pinfunction "S1_S5") (pintype "bidirectional"))
      (node (ref "Q407") (pin "S1") (pinfunction "S1_S1") (pintype "bidirectional"))
      (node (ref "Q407") (pin "S2") (pinfunction "S1_S2") (pintype "bidirectional"))
      (node (ref "Q407") (pin "S3") (pinfunction "S1_S3") (pintype "bidirectional"))
      (node (ref "Q407") (pin "S4") (pinfunction "S1_S4") (pintype "bidirectional"))
      (node (ref "Q407") (pin "S5") (pinfunction "S1_S5") (pintype "bidirectional"))
      (node (ref "Q408") (pin "S1") (pinfunction "S1_S1") (pintype "bidirectional"))
      (node (ref "Q408") (pin "S2") (pinfunction "S1_S2") (pintype "bidirectional"))
      (node (ref "Q408") (pin "S3") (pinfunction "S1_S3") (pintype "bidirectional"))
      (node (ref "Q408") (pin "S4") (pinfunction "S1_S4") (pintype "bidirectional"))
      (node (ref "Q408") (pin "S5") (pinfunction "S1_S5") (pintype "bidirectional"))
      (node (ref "Q409") (pin "S1") (pinfunction "S1_S1") (pintype "bidirectional"))
      (node (ref "Q409") (pin "S2") (pinfunction "S1_S2") (pintype "bidirectional"))
      (node (ref "Q409") (pin "S3") (pinfunction "S1_S3") (pintype "bidirectional"))
      (node (ref "Q409") (pin "S4") (pinfunction "S1_S4") (pintype "bidirectional"))
      (node (ref "Q409") (pin "S5") (pinfunction "S1_S5") (pintype "bidirectional"))
      (node (ref "R104") (pin "P$1") (pinfunction "P$1_P$1") (pintype "bidirectional"))
      (node (ref "R105") (pin "P$1") (pinfunction "P$1_P$1") (pintype "bidirectional"))
      (node (ref "R107") (pin "P$1") (pinfunction "P$1_P$1") (pintype "bidirectional"))
      (node (ref "R108") (pin "P$1") (pinfunction "P$1_P$1") (pintype "bidirectional"))
      (node (ref "R110") (pin "P$1") (pinfunction "P$1_P$1") (pintype "bidirectional"))
      (node (ref "R114") (pin "P$2") (pinfunction "P$2_P$2") (pintype "bidirectional"))
      (node (ref "R116") (pin "P$1") (pinfunction "P$1_P$1") (pintype "bidirectional"))
      (node (ref "R118") (pin "P$1") (pinfunction "P$1_P$1") (pintype "bidirectional"))
      (node (ref "R121") (pin "P$1") (pinfunction "P$1_P$1") (pintype "bidirectional"))
      (node (ref "R302") (pin "P$1") (pinfunction "P$1_P$1") (pintype "bidirectional"))
      (node (ref "R304") (pin "P$1") (pinfunction "P$1_P$1") (pintype "bidirectional"))
      (node (ref "R401") (pin "P$1") (pinfunction "P$1_P$1") (pintype "bidirectional"))
      (node (ref "R402") (pin "P$1") (pinfunction "P$1_P$1") (pintype "bidirectional"))
      (node (ref "R403") (pin "P$1") (pinfunction "P$1_P$1") (pintype "bidirectional"))
      (node (ref "R404") (pin "P$1") (pinfunction "P$1_P$1") (pintype "bidirectional"))
      (node (ref "R405") (pin "P$1") (pinfunction "P$1_P$1") (pintype "bidirectional"))
      (node (ref "R406") (pin "P$1") (pinfunction "P$1_P$1") (pintype "bidirectional"))
      (node (ref "R407") (pin "P$1") (pinfunction "P$1_P$1") (pintype "bidirectional"))
      (node (ref "R408") (pin "P$1") (pinfunction "P$1_P$1") (pintype "bidirectional"))
      (node (ref "R428") (pin "P$1") (pinfunction "P$1_P$1") (pintype "bidirectional"))
      (node (ref "R430") (pin "P$1") (pinfunction "P$1_P$1") (pintype "bidirectional"))
      (node (ref "R505") (pin "P$1") (pinfunction "P$1_P$1") (pintype "bidirectional"))
      (node (ref "R507") (pin "P$2") (pinfunction "P$2_P$2") (pintype "bidirectional"))
      (node (ref "R510") (pin "P$1") (pinfunction "P$1_P$1") (pintype "bidirectional"))
      (node (ref "R511") (pin "P$1") (pinfunction "P$1_P$1") (pintype "bidirectional"))
      (node (ref "U101") (pin "3") (pinfunction "GND_3") (pintype "bidirectional"))
      (node (ref "U102") (pin "14") (pinfunction "GND_14") (pintype "bidirectional"))
      (node (ref "U102") (pin "24") (pinfunction "GNDA_24") (pintype "bidirectional"))
      (node (ref "U102") (pin "3") (pinfunction "GND_3") (pintype "bidirectional"))
      (node (ref "U102") (pin "44") (pinfunction "GND_44") (pintype "bidirectional"))
      (node (ref "U102") (pin "53") (pinfunction "PLL_GND_53") (pintype "bidirectional"))
      (node (ref "U102") (pin "54") (pinfunction "TEST_54") (pintype "bidirectional"))
      (node (ref "U102") (pin "62") (pinfunction "GND_62") (pintype "bidirectional"))
      (node (ref "U102") (pin "73") (pinfunction "GND_73") (pintype "bidirectional"))
      (node (ref "U102") (pin "PAD") (pinfunction "GNDP_PAD") (pintype "bidirectional"))
      (node (ref "U201") (pin "2") (pinfunction "GND_2") (pintype "bidirectional"))
      (node (ref "U202") (pin "2") (pinfunction "GND_2") (pintype "bidirectional"))
      (node (ref "U203") (pin "2") (pinfunction "GND_2") (pintype "bidirectional"))
      (node (ref "U204") (pin "2") (pinfunction "GND_2") (pintype "bidirectional"))
      (node (ref "U205") (pin "4") (pinfunction "GND_4") (pintype "bidirectional"))
      (node (ref "U206") (pin "4") (pinfunction "GND_4") (pintype "bidirectional"))
      (node (ref "U207") (pin "4") (pinfunction "GND_4") (pintype "bidirectional"))
      (node (ref "U208") (pin "4") (pinfunction "GND_4") (pintype "bidirectional"))
      (node (ref "U301") (pin "2") (pinfunction "GND_2") (pintype "bidirectional"))
      (node (ref "U301") (pin "4") (pinfunction "SHDN_4") (pintype "bidirectional"))
      (node (ref "U301") (pin "6") (pinfunction "GND_6") (pintype "bidirectional"))
      (node (ref "U301") (pin "7") (pinfunction "GND_7") (pintype "bidirectional"))
      (node (ref "U302") (pin "5") (pinfunction "GND_5") (pintype "bidirectional"))
      (node (ref "U302") (pin "6") (pinfunction "GND_6") (pintype "bidirectional"))
      (node (ref "U302") (pin "7") (pinfunction "GND_7") (pintype "bidirectional"))
      (node (ref "U302") (pin "8") (pinfunction "GND_8") (pintype "bidirectional"))
      (node (ref "U303") (pin "5") (pinfunction "GND_5") (pintype "bidirectional"))
      (node (ref "U303") (pin "6") (pinfunction "GND_6") (pintype "bidirectional"))
      (node (ref "U303") (pin "7") (pinfunction "GND_7") (pintype "bidirectional"))
      (node (ref "U303") (pin "8") (pinfunction "GND_8") (pintype "bidirectional"))
      (node (ref "U401") (pin "4") (pinfunction "GNDI_4") (pintype "bidirectional"))
      (node (ref "U401") (pin "9") (pinfunction "GNB_9") (pintype "bidirectional"))
      (node (ref "U402") (pin "4") (pinfunction "GNDI_4") (pintype "bidirectional"))
      (node (ref "U402") (pin "9") (pinfunction "GNB_9") (pintype "bidirectional"))
      (node (ref "U403") (pin "4") (pinfunction "GNDI_4") (pintype "bidirectional"))
      (node (ref "U403") (pin "9") (pinfunction "GNB_9") (pintype "bidirectional"))
      (node (ref "U404") (pin "4") (pinfunction "GNDI_4") (pintype "bidirectional"))
      (node (ref "U404") (pin "9") (pinfunction "GNB_9") (pintype "bidirectional"))
      (node (ref "U405") (pin "2") (pinfunction "P$1_2") (pintype "bidirectional"))
      (node (ref "U405") (pin "3") (pinfunction "P$1_3") (pintype "bidirectional"))
      (node (ref "U406") (pin "2") (pinfunction "P$1_2") (pintype "bidirectional"))
      (node (ref "U406") (pin "3") (pinfunction "P$1_3") (pintype "bidirectional"))
      (node (ref "U407") (pin "3") (pinfunction "CA_3") (pintype "bidirectional"))
      (node (ref "U407") (pin "5") (pinfunction "GNB_5") (pintype "bidirectional"))
      (node (ref "U501") (pin "2") (pinfunction "GND_2") (pintype "bidirectional"))
      (node (ref "U501") (pin "PAD") (pinfunction "GNDP_PAD") (pintype "bidirectional"))
    )
    (net (code "32") (name "HALL_UX") (class "Default")
      (node (ref "U102") (pin "38") (pinfunction "HALL_UX_38") (pintype "bidirectional"))
      (node (ref "U207") (pin "2") (pinfunction "Y_2") (pintype "output"))
    )
    (net (code "33") (name "HALL_V") (class "Default")
      (node (ref "U102") (pin "37") (pinfunction "HALL_V_37") (pintype "bidirectional"))
      (node (ref "U207") (pin "5") (pinfunction "Y_5") (pintype "output"))
    )
    (net (code "34") (name "HALL_WY") (class "Default")
      (node (ref "U102") (pin "36") (pinfunction "HALL_WY_36") (pintype "bidirectional"))
      (node (ref "U207") (pin "7") (pinfunction "Y_7") (pintype "output"))
    )
    (net (code "35") (name "INT") (class "Default")
      (node (ref "J501") (pin "5") (pinfunction "S_5") (pintype "passive"))
      (node (ref "JP507") (pin "2") (pinfunction "2_2") (pintype "passive"))
      (node (ref "U102") (pin "12") (pinfunction "STATUS_12") (pintype "bidirectional"))
    )
    (net (code "36") (name "MISO") (class "Default")
      (node (ref "J501") (pin "4") (pinfunction "S_4") (pintype "passive"))
      (node (ref "JP501") (pin "2") (pinfunction "2_2") (pintype "passive"))
      (node (ref "U102") (pin "9") (pinfunction "SPI_MISO_9") (pintype "bidirectional"))
    )
    (net (code "37") (name "MOSI") (class "Default")
      (node (ref "J501") (pin "3") (pinfunction "S_3") (pintype "passive"))
      (node (ref "JP502") (pin "2") (pinfunction "2_2") (pintype "passive"))
      (node (ref "U102") (pin "8") (pinfunction "SPI_MOSI_8") (pintype "bidirectional"))
    )
    (net (code "38") (name "Net-(C307-AN)") (class "Default")
      (node (ref "C305") (pin "P$1") (pinfunction "P$1_P$1") (pintype "bidirectional"))
      (node (ref "C307") (pin "+") (pinfunction "AN_+") (pintype "bidirectional"))
      (node (ref "L301") (pin "2") (pinfunction "P$2_2") (pintype "bidirectional"))
      (node (ref "R303") (pin "P$2") (pinfunction "P$2_P$2") (pintype "bidirectional"))
      (node (ref "R305") (pin "P$2") (pinfunction "P$2_P$2") (pintype "bidirectional"))
      (node (ref "U302") (pin "1") (pinfunction "EN_1") (pintype "bidirectional"))
      (node (ref "U302") (pin "2") (pinfunction "VIN_2") (pintype "bidirectional"))
      (node (ref "U303") (pin "1") (pinfunction "EN_1") (pintype "bidirectional"))
      (node (ref "U303") (pin "2") (pinfunction "VIN_2") (pintype "bidirectional"))
    )
    (net (code "39") (name "Net-(D101-3)") (class "Default")
      (node (ref "C118") (pin "P$1") (pinfunction "P$1_P$1") (pintype "bidirectional"))
      (node (ref "D101") (pin "P$3") (pinfunction "3_P$3") (pintype "bidirectional"))
      (node (ref "R116") (pin "P$2") (pinfunction "P$2_P$2") (pintype "bidirectional"))
      (node (ref "R119") (pin "P$1") (pinfunction "P$1_P$1") (pintype "bidirectional"))
      (node (ref "U102") (pin "20") (pinfunction "ADC_VM_20") (pintype "bidirectional"))
    )
    (net (code "40") (name "Net-(D302-AN)") (class "Default")
      (node (ref "D302") (pin "A") (pinfunction "AN_A") (pintype "bidirectional"))
      (node (ref "R305") (pin "P$1") (pinfunction "P$1_P$1") (pintype "bidirectional"))
      (node (ref "U302") (pin "4") (pinfunction "FLG_4") (pintype "bidirectional"))
      (node (ref "U303") (pin "4") (pinfunction "FLG_4") (pintype "bidirectional"))
    )
    (net (code "41") (name "Net-(D401-PadA)") (class "Default")
      (node (ref "D401") (pin "A") (pinfunction "A_A") (pintype "passive"))
      (node (ref "R409") (pin "P$2") (pinfunction "P$2_P$2") (pintype "bidirectional"))
    )
    (net (code "42") (name "Net-(D402-PadA)") (class "Default")
      (node (ref "D402") (pin "A") (pinfunction "A_A") (pintype "passive"))
      (node (ref "R410") (pin "P$2") (pinfunction "P$2_P$2") (pintype "bidirectional"))
    )
    (net (code "43") (name "Net-(D403-PadA)") (class "Default")
      (node (ref "D403") (pin "A") (pinfunction "A_A") (pintype "passive"))
      (node (ref "R411") (pin "P$2") (pinfunction "P$2_P$2") (pintype "bidirectional"))
    )
    (net (code "44") (name "Net-(D404-PadA)") (class "Default")
      (node (ref "D404") (pin "A") (pinfunction "A_A") (pintype "passive"))
      (node (ref "R412") (pin "P$2") (pinfunction "P$2_P$2") (pintype "bidirectional"))
    )
    (net (code "45") (name "Net-(D501-AN)") (class "Default")
      (node (ref "D501") (pin "A") (pinfunction "AN_A") (pintype "bidirectional"))
      (node (ref "R502") (pin "P$1") (pinfunction "P$1_P$1") (pintype "bidirectional"))
    )
    (net (code "46") (name "Net-(D501-CA)") (class "Default")
      (node (ref "D501") (pin "C") (pinfunction "CA_C") (pintype "bidirectional"))
      (node (ref "U501") (pin "14") (pinfunction "(GPIO0-TXT)GPIO7-~{CS7}_14") (pintype "bidirectional"))
    )
    (net (code "47") (name "Net-(D502-AN)") (class "Default")
      (node (ref "D502") (pin "A") (pinfunction "AN_A") (pintype "bidirectional"))
      (node (ref "R503") (pin "P$1") (pinfunction "P$1_P$1") (pintype "bidirectional"))
    )
    (net (code "48") (name "Net-(D502-CA)") (class "Default")
      (node (ref "D502") (pin "C") (pinfunction "CA_C") (pintype "bidirectional"))
      (node (ref "U501") (pin "13") (pinfunction "(GPIO1-RXT)GPIO8-~{CS8}-SPIACT_13") (pintype "bidirectional"))
    )
    (net (code "49") (name "Net-(D503-Pad4)") (class "Default")
      (node (ref "D503") (pin "4") (pinfunction "4_4") (pintype "bidirectional"))
      (node (ref "J503") (pin "VBUS") (pinfunction "VBUS_VBUS") (pintype "bidirectional"))
      (node (ref "R506") (pin "P$1") (pinfunction "P$1_P$1") (pintype "bidirectional"))
    )
    (net (code "50") (name "Net-(J201B-S)") (class "Default")
      (node (ref "J201") (pin "2") (pinfunction "S_2") (pintype "passive"))
      (node (ref "R201") (pin "P$1") (pinfunction "P$1_P$1") (pintype "bidirectional"))
    )
    (net (code "51") (name "Net-(J201C-S)") (class "Default")
      (node (ref "J201") (pin "3") (pinfunction "S_3") (pintype "passive"))
      (node (ref "R202") (pin "P$1") (pinfunction "P$1_P$1") (pintype "bidirectional"))
    )
    (net (code "52") (name "Net-(J201D-S)") (class "Default")
      (node (ref "J201") (pin "4") (pinfunction "S_4") (pintype "passive"))
      (node (ref "R203") (pin "P$1") (pinfunction "P$1_P$1") (pintype "bidirectional"))
    )
    (net (code "53") (name "Net-(J202B-S)") (class "Default")
      (node (ref "J202") (pin "2") (pinfunction "S_2") (pintype "passive"))
      (node (ref "R204") (pin "P$1") (pinfunction "P$1_P$1") (pintype "bidirectional"))
    )
    (net (code "54") (name "Net-(J202C-S)") (class "Default")
      (node (ref "J202") (pin "3") (pinfunction "S_3") (pintype "passive"))
      (node (ref "R205") (pin "P$1") (pinfunction "P$1_P$1") (pintype "bidirectional"))
    )
    (net (code "55") (name "Net-(J202D-S)") (class "Default")
      (node (ref "J202") (pin "4") (pinfunction "S_4") (pintype "passive"))
      (node (ref "R206") (pin "P$1") (pinfunction "P$1_P$1") (pintype "bidirectional"))
    )
    (net (code "56") (name "Net-(J203B-S)") (class "Default")
      (node (ref "J203") (pin "2") (pinfunction "S_2") (pintype "passive"))
      (node (ref "R207") (pin "P$1") (pinfunction "P$1_P$1") (pintype "bidirectional"))
    )
    (net (code "57") (name "Net-(J203C-S)") (class "Default")
      (node (ref "J203") (pin "3") (pinfunction "S_3") (pintype "passive"))
      (node (ref "R208") (pin "P$1") (pinfunction "P$1_P$1") (pintype "bidirectional"))
    )
    (net (code "58") (name "Net-(J203D-S)") (class "Default")
      (node (ref "J203") (pin "4") (pinfunction "S_4") (pintype "passive"))
      (node (ref "R209") (pin "P$1") (pinfunction "P$1_P$1") (pintype "bidirectional"))
    )
    (net (code "59") (name "Net-(J204B-S)") (class "Default")
      (node (ref "J204") (pin "2") (pinfunction "S_2") (pintype "passive"))
      (node (ref "R210") (pin "P$1") (pinfunction "P$1_P$1") (pintype "bidirectional"))
    )
    (net (code "60") (name "Net-(J204C-S)") (class "Default")
      (node (ref "J204") (pin "3") (pinfunction "S_3") (pintype "passive"))
      (node (ref "R211") (pin "P$1") (pinfunction "P$1_P$1") (pintype "bidirectional"))
    )
    (net (code "61") (name "Net-(J204D-S)") (class "Default")
      (node (ref "J204") (pin "4") (pinfunction "S_4") (pintype "passive"))
      (node (ref "R212") (pin "P$1") (pinfunction "P$1_P$1") (pintype "bidirectional"))
    )
    (net (code "62") (name "Net-(J205B-S)") (class "Default")
      (node (ref "J205") (pin "2") (pinfunction "S_2") (pintype "passive"))
      (node (ref "R213") (pin "P$1") (pinfunction "P$1_P$1") (pintype "bidirectional"))
    )
    (net (code "63") (name "Net-(J205C-S)") (class "Default")
      (node (ref "J205") (pin "3") (pinfunction "S_3") (pintype "passive"))
      (node (ref "R218") (pin "P$1") (pinfunction "P$1_P$1") (pintype "bidirectional"))
    )
    (net (code "64") (name "Net-(J205D-S)") (class "Default")
      (node (ref "J205") (pin "4") (pinfunction "S_4") (pintype "passive"))
      (node (ref "R227") (pin "P$1") (pinfunction "P$1_P$1") (pintype "bidirectional"))
    )
    (net (code "65") (name "Net-(J403B-S)") (class "Default")
      (node (ref "J403") (pin "2") (pinfunction "S_2") (pintype "passive"))
      (node (ref "P406") (pin "H1") (pinfunction "S_H1") (pintype "passive"))
      (node (ref "P406") (pin "H10") (pinfunction "S_H10") (pintype "passive"))
      (node (ref "P406") (pin "H11") (pinfunction "S_H11") (pintype "passive"))
      (node (ref "P406") (pin "H12") (pinfunction "S_H12") (pintype "passive"))
      (node (ref "P406") (pin "H2") (pinfunction "S_H2") (pintype "passive"))
      (node (ref "P406") (pin "H3") (pinfunction "S_H3") (pintype "passive"))
      (node (ref "P406") (pin "H4") (pinfunction "S_H4") (pintype "passive"))
      (node (ref "P406") (pin "H5") (pinfunction "S_H5") (pintype "passive"))
      (node (ref "P406") (pin "H6") (pinfunction "S_H6") (pintype "passive"))
      (node (ref "P406") (pin "H7") (pinfunction "S_H7") (pintype "passive"))
      (node (ref "P406") (pin "H8") (pinfunction "S_H8") (pintype "passive"))
      (node (ref "P406") (pin "H9") (pinfunction "S_H9") (pintype "passive"))
      (node (ref "P406") (pin "PAD") (pinfunction "S_PAD") (pintype "passive"))
      (node (ref "Q409") (pin "D1") (pinfunction "D1_D1") (pintype "bidirectional"))
      (node (ref "Q409") (pin "D2") (pinfunction "D1_D2") (pintype "bidirectional"))
      (node (ref "Q409") (pin "D3") (pinfunction "D1_D3") (pintype "bidirectional"))
      (node (ref "Q409") (pin "D4") (pinfunction "D1_D4") (pintype "bidirectional"))
    )
    (net (code "66") (name "Net-(J504A-S)") (class "Default")
      (node (ref "J504") (pin "1") (pinfunction "S_1") (pintype "passive"))
      (node (ref "R504") (pin "P$1") (pinfunction "P$1_P$1") (pintype "bidirectional"))
    )
    (net (code "67") (name "Net-(J506A-S)") (class "Default")
      (node (ref "J506") (pin "1") (pinfunction "S_1") (pintype "passive"))
      (node (ref "R508") (pin "P$1") (pinfunction "P$1_P$1") (pintype "bidirectional"))
    )
    (net (code "68") (name "Net-(J506B-S)") (class "Default")
      (node (ref "J506") (pin "2") (pinfunction "S_2") (pintype "passive"))
      (node (ref "R509") (pin "P$1") (pinfunction "P$1_P$1") (pintype "bidirectional"))
    )
    (net (code "69") (name "Net-(L301-P$1)") (class "Default")
      (node (ref "D301") (pin "C") (pinfunction "C_C") (pintype "bidirectional"))
      (node (ref "L301") (pin "1") (pinfunction "P$1_1") (pintype "bidirectional"))
      (node (ref "U301") (pin "8") (pinfunction "SW_8") (pintype "bidirectional"))
    )
    (net (code "70") (name "Net-(Q401-G1)") (class "Default")
      (node (ref "Q401") (pin "G") (pinfunction "G1_G") (pintype "bidirectional"))
      (node (ref "R413") (pin "P$2") (pinfunction "P$2_P$2") (pintype "bidirectional"))
    )
    (net (code "71") (name "Net-(Q402-G1)") (class "Default")
      (node (ref "Q402") (pin "G") (pinfunction "G1_G") (pintype "bidirectional"))
      (node (ref "R414") (pin "P$2") (pinfunction "P$2_P$2") (pintype "bidirectional"))
    )
    (net (code "72") (name "Net-(Q403-G1)") (class "Default")
      (node (ref "Q403") (pin "G") (pinfunction "G1_G") (pintype "bidirectional"))
      (node (ref "R415") (pin "P$2") (pinfunction "P$2_P$2") (pintype "bidirectional"))
    )
    (net (code "73") (name "Net-(Q404-G1)") (class "Default")
      (node (ref "Q404") (pin "G") (pinfunction "G1_G") (pintype "bidirectional"))
      (node (ref "R416") (pin "P$2") (pinfunction "P$2_P$2") (pintype "bidirectional"))
    )
    (net (code "74") (name "Net-(Q405-G1)") (class "Default")
      (node (ref "Q405") (pin "G") (pinfunction "G1_G") (pintype "bidirectional"))
      (node (ref "R417") (pin "P$2") (pinfunction "P$2_P$2") (pintype "bidirectional"))
    )
    (net (code "75") (name "Net-(Q406-G1)") (class "Default")
      (node (ref "Q406") (pin "G") (pinfunction "G1_G") (pintype "bidirectional"))
      (node (ref "R418") (pin "P$2") (pinfunction "P$2_P$2") (pintype "bidirectional"))
    )
    (net (code "76") (name "Net-(Q407-G1)") (class "Default")
      (node (ref "Q407") (pin "G") (pinfunction "G1_G") (pintype "bidirectional"))
      (node (ref "R419") (pin "P$2") (pinfunction "P$2_P$2") (pintype "bidirectional"))
    )
    (net (code "77") (name "Net-(Q408-G1)") (class "Default")
      (node (ref "Q408") (pin "G") (pinfunction "G1_G") (pintype "bidirectional"))
      (node (ref "R420") (pin "P$2") (pinfunction "P$2_P$2") (pintype "bidirectional"))
    )
    (net (code "78") (name "Net-(Q409-G1)") (class "Default")
      (node (ref "Q409") (pin "G") (pinfunction "G1_G") (pintype "bidirectional"))
      (node (ref "R431") (pin "P$2") (pinfunction "P$2_P$2") (pintype "bidirectional"))
    )
    (net (code "79") (name "Net-(R421-PadSENSE+)") (class "Default")
      (node (ref "R421") (pin "SENSE+") (pinfunction "SENSE+_SENSE+") (pintype "bidirectional"))
      (node (ref "R424") (pin "P$1") (pinfunction "P$1_P$1") (pintype "bidirectional"))
    )
    (net (code "80") (name "Net-(R421-PadSENSE-)") (class "Default")
      (node (ref "R421") (pin "SENSE-") (pinfunction "SENSE-_SENSE-") (pintype "bidirectional"))
      (node (ref "R423") (pin "P$1") (pinfunction "P$1_P$1") (pintype "bidirectional"))
    )
    (net (code "81") (name "Net-(R422-PadSENSE+)") (class "Default")
      (node (ref "R422") (pin "SENSE+") (pinfunction "SENSE+_SENSE+") (pintype "bidirectional"))
      (node (ref "R426") (pin "P$1") (pinfunction "P$1_P$1") (pintype "bidirectional"))
    )
    (net (code "82") (name "Net-(R422-PadSENSE-)") (class "Default")
      (node (ref "R422") (pin "SENSE-") (pinfunction "SENSE-_SENSE-") (pintype "bidirectional"))
      (node (ref "R425") (pin "P$1") (pinfunction "P$1_P$1") (pintype "bidirectional"))
    )
    (net (code "83") (name "Net-(R431-PadP$1)") (class "Default")
      (node (ref "R431") (pin "P$1") (pinfunction "P$1_P$1") (pintype "bidirectional"))
      (node (ref "U407") (pin "6") (pinfunction "VO_6") (pintype "bidirectional"))
      (node (ref "U407") (pin "7") (pinfunction "VO_7") (pintype "bidirectional"))
    )
    (net (code "84") (name "Net-(U101-EN)") (class "Default")
      (node (ref "R101") (pin "P$1") (pinfunction "P$1_P$1") (pintype "bidirectional"))
      (node (ref "U101") (pin "1") (pinfunction "EN_1") (pintype "bidirectional"))
    )
    (net (code "85") (name "Net-(U101-OUT)") (class "Default")
      (node (ref "U101") (pin "4") (pinfunction "OUT_4") (pintype "bidirectional"))
      (node (ref "U102") (pin "51") (pinfunction "CLK_51") (pintype "bidirectional"))
    )
    (net (code "86") (name "Net-(U102A-AGPI_A)") (class "Default")
      (node (ref "C114") (pin "P$1") (pinfunction "P$1_P$1") (pintype "bidirectional"))
      (node (ref "R111") (pin "P$1") (pinfunction "P$1_P$1") (pintype "bidirectional"))
      (node (ref "U102") (pin "21") (pinfunction "AGPI_A_21") (pintype "bidirectional"))
    )
    (net (code "87") (name "Net-(U102A-AGPI_B)") (class "Default")
      (node (ref "C115") (pin "P$1") (pinfunction "P$1_P$1") (pintype "bidirectional"))
      (node (ref "R112") (pin "P$2") (pinfunction "P$2_P$2") (pintype "bidirectional"))
      (node (ref "U102") (pin "22") (pinfunction "AGPI_B_22") (pintype "bidirectional"))
    )
    (net (code "88") (name "Net-(U102B-~{RST})") (class "Default")
      (node (ref "R102") (pin "P$2") (pinfunction "P$2_P$2") (pintype "bidirectional"))
      (node (ref "U102") (pin "50") (pinfunction "~{RST}_50") (pintype "bidirectional"))
    )
    (net (code "89") (name "Net-(U102D-ADC_I0_NEG)") (class "Default")
      (node (ref "R117") (pin "P$1") (pinfunction "P$1_P$1") (pintype "bidirectional"))
      (node (ref "R118") (pin "P$2") (pinfunction "P$2_P$2") (pintype "bidirectional"))
      (node (ref "U102") (pin "17") (pinfunction "ADC_I0_NEG_17") (pintype "bidirectional"))
    )
    (net (code "90") (name "Net-(U102D-ADC_I0_POS)") (class "Default")
      (node (ref "C116") (pin "P$1") (pinfunction "P$1_P$1") (pintype "bidirectional"))
      (node (ref "R113") (pin "P$1") (pinfunction "P$1_P$1") (pintype "bidirectional"))
      (node (ref "U102") (pin "16") (pinfunction "ADC_I0_POS_16") (pintype "bidirectional"))
    )
    (net (code "91") (name "Net-(U102D-ADC_I1_NEG)") (class "Default")
      (node (ref "R120") (pin "P$1") (pinfunction "P$1_P$1") (pintype "bidirectional"))
      (node (ref "R121") (pin "P$2") (pinfunction "P$2_P$2") (pintype "bidirectional"))
      (node (ref "U102") (pin "19") (pinfunction "ADC_I1_NEG_19") (pintype "bidirectional"))
    )
    (net (code "92") (name "Net-(U102D-ADC_I1_POS)") (class "Default")
      (node (ref "C117") (pin "P$1") (pinfunction "P$1_P$1") (pintype "bidirectional"))
      (node (ref "R115") (pin "P$1") (pinfunction "P$1_P$1") (pintype "bidirectional"))
      (node (ref "U102") (pin "18") (pinfunction "ADC_I1_POS_18") (pintype "bidirectional"))
    )
    (net (code "93") (name "Net-(U102D-AENC_UX_NEG)") (class "Default")
      (node (ref "R103") (pin "P$1") (pinfunction "P$1_P$1") (pintype "bidirectional"))
      (node (ref "R104") (pin "P$2") (pinfunction "P$2_P$2") (pintype "bidirectional"))
      (node (ref "U102") (pin "26") (pinfunction "AENC_UX_NEG_26") (pintype "bidirectional"))
    )
    (net (code "94") (name "Net-(U102D-AENC_VN_NEG)") (class "Default")
      (node (ref "R106") (pin "P$1") (pinfunction "P$1_P$1") (pintype "bidirectional"))
      (node (ref "R107") (pin "P$2") (pinfunction "P$2_P$2") (pintype "bidirectional"))
      (node (ref "U102") (pin "28") (pinfunction "AENC_VN_NEG_28") (pintype "bidirectional"))
    )
    (net (code "95") (name "Net-(U102D-AENC_WY_NEG)") (class "Default")
      (node (ref "R109") (pin "P$1") (pinfunction "P$1_P$1") (pintype "bidirectional"))
      (node (ref "R110") (pin "P$2") (pinfunction "P$2_P$2") (pintype "bidirectional"))
      (node (ref "U102") (pin "30") (pinfunction "AENC_WY_NEG_30") (pintype "bidirectional"))
    )
    (net (code "96") (name "Net-(U102D-PWM_IDLE_H)") (class "Default")
      (node (ref "R105") (pin "P$2") (pinfunction "P$2_P$2") (pintype "bidirectional"))
      (node (ref "U102") (pin "59") (pinfunction "PWM_IDLE_H_59") (pintype "bidirectional"))
    )
    (net (code "97") (name "Net-(U102D-PWM_IDLE_L)") (class "Default")
      (node (ref "R108") (pin "P$2") (pinfunction "P$2_P$2") (pintype "bidirectional"))
      (node (ref "U102") (pin "60") (pinfunction "PWM_IDLE_L_60") (pintype "bidirectional"))
    )
    (net (code "98") (name "Net-(U201-1)") (class "Default")
      (node (ref "C206") (pin "P$1") (pinfunction "P$1_P$1") (pintype "bidirectional"))
      (node (ref "R201") (pin "P$2") (pinfunction "P$2_P$2") (pintype "bidirectional"))
      (node (ref "R214") (pin "P$2") (pinfunction "P$2_P$2") (pintype "bidirectional"))
      (node (ref "U201") (pin "6") (pinfunction "1_6") (pintype "bidirectional"))
      (node (ref "U205") (pin "1") (pinfunction "A_1") (pintype "input"))
    )
    (net (code "99") (name "Net-(U201-2)") (class "Default")
      (node (ref "C218") (pin "P$1") (pinfunction "P$1_P$1") (pintype "bidirectional"))
      (node (ref "R203") (pin "P$2") (pinfunction "P$2_P$2") (pintype "bidirectional"))
      (node (ref "R223") (pin "P$2") (pinfunction "P$2_P$2") (pintype "bidirectional"))
      (node (ref "U201") (pin "1") (pinfunction "2_1") (pintype "bidirectional"))
      (node (ref "U205") (pin "6") (pinfunction "A_6") (pintype "input"))
    )
    (net (code "100") (name "Net-(U202-1)") (class "Default")
      (node (ref "C207") (pin "P$1") (pinfunction "P$1_P$1") (pintype "bidirectional"))
      (node (ref "R204") (pin "P$2") (pinfunction "P$2_P$2") (pintype "bidirectional"))
      (node (ref "R215") (pin "P$2") (pinfunction "P$2_P$2") (pintype "bidirectional"))
      (node (ref "U202") (pin "6") (pinfunction "1_6") (pintype "bidirectional"))
      (node (ref "U206") (pin "1") (pinfunction "A_1") (pintype "input"))
    )
    (net (code "101") (name "Net-(U202-2)") (class "Default")
      (node (ref "C219") (pin "P$1") (pinfunction "P$1_P$1") (pintype "bidirectional"))
      (node (ref "R206") (pin "P$2") (pinfunction "P$2_P$2") (pintype "bidirectional"))
      (node (ref "R224") (pin "P$2") (pinfunction "P$2_P$2") (pintype "bidirectional"))
      (node (ref "U202") (pin "1") (pinfunction "2_1") (pintype "bidirectional"))
      (node (ref "U206") (pin "6") (pinfunction "A_6") (pintype "input"))
    )
    (net (code "102") (name "Net-(U203-1)") (class "Default")
      (node (ref "C208") (pin "P$1") (pinfunction "P$1_P$1") (pintype "bidirectional"))
      (node (ref "R207") (pin "P$2") (pinfunction "P$2_P$2") (pintype "bidirectional"))
      (node (ref "R216") (pin "P$2") (pinfunction "P$2_P$2") (pintype "bidirectional"))
      (node (ref "U203") (pin "6") (pinfunction "1_6") (pintype "bidirectional"))
      (node (ref "U207") (pin "1") (pinfunction "A_1") (pintype "input"))
    )
    (net (code "103") (name "Net-(U203-2)") (class "Default")
      (node (ref "C220") (pin "P$1") (pinfunction "P$1_P$1") (pintype "bidirectional"))
      (node (ref "R209") (pin "P$2") (pinfunction "P$2_P$2") (pintype "bidirectional"))
      (node (ref "R225") (pin "P$2") (pinfunction "P$2_P$2") (pintype "bidirectional"))
      (node (ref "U203") (pin "1") (pinfunction "2_1") (pintype "bidirectional"))
      (node (ref "U207") (pin "6") (pinfunction "A_6") (pintype "input"))
    )
    (net (code "104") (name "Net-(U204-1)") (class "Default")
      (node (ref "C209") (pin "P$1") (pinfunction "P$1_P$1") (pintype "bidirectional"))
      (node (ref "R210") (pin "P$2") (pinfunction "P$2_P$2") (pintype "bidirectional"))
      (node (ref "R217") (pin "P$2") (pinfunction "P$2_P$2") (pintype "bidirectional"))
      (node (ref "U204") (pin "6") (pinfunction "1_6") (pintype "bidirectional"))
      (node (ref "U208") (pin "1") (pinfunction "A_1") (pintype "input"))
    )
    (net (code "105") (name "Net-(U204-2)") (class "Default")
      (node (ref "C221") (pin "P$1") (pinfunction "P$1_P$1") (pintype "bidirectional"))
      (node (ref "R212") (pin "P$2") (pinfunction "P$2_P$2") (pintype "bidirectional"))
      (node (ref "R226") (pin "P$2") (pinfunction "P$2_P$2") (pintype "bidirectional"))
      (node (ref "U204") (pin "1") (pinfunction "2_1") (pintype "bidirectional"))
      (node (ref "U208") (pin "6") (pinfunction "A_6") (pintype "input"))
    )
    (net (code "106") (name "Net-(U205B-A)") (class "Default")
      (node (ref "C210") (pin "P$1") (pinfunction "P$1_P$1") (pintype "bidirectional"))
      (node (ref "R202") (pin "P$2") (pinfunction "P$2_P$2") (pintype "bidirectional"))
      (node (ref "R219") (pin "P$2") (pinfunction "P$2_P$2") (pintype "bidirectional"))
      (node (ref "U201") (pin "4") (pinfunction "4_4") (pintype "bidirectional"))
      (node (ref "U205") (pin "3") (pinfunction "A_3") (pintype "input"))
    )
    (net (code "107") (name "Net-(U206B-A)") (class "Default")
      (node (ref "C211") (pin "P$1") (pinfunction "P$1_P$1") (pintype "bidirectional"))
      (node (ref "R205") (pin "P$2") (pinfunction "P$2_P$2") (pintype "bidirectional"))
      (node (ref "R220") (pin "P$2") (pinfunction "P$2_P$2") (pintype "bidirectional"))
      (node (ref "U202") (pin "4") (pinfunction "4_4") (pintype "bidirectional"))
      (node (ref "U206") (pin "3") (pinfunction "A_3") (pintype "input"))
    )
    (net (code "108") (name "Net-(U207B-A)") (class "Default")
      (node (ref "C212") (pin "P$1") (pinfunction "P$1_P$1") (pintype "bidirectional"))
      (node (ref "R208") (pin "P$2") (pinfunction "P$2_P$2") (pintype "bidirectional"))
      (node (ref "R221") (pin "P$2") (pinfunction "P$2_P$2") (pintype "bidirectional"))
      (node (ref "U203") (pin "4") (pinfunction "4_4") (pintype "bidirectional"))
      (node (ref "U207") (pin "3") (pinfunction "A_3") (pintype "input"))
    )
    (net (code "109") (name "Net-(U208B-A)") (class "Default")
      (node (ref "C213") (pin "P$1") (pinfunction "P$1_P$1") (pintype "bidirectional"))
      (node (ref "R211") (pin "P$2") (pinfunction "P$2_P$2") (pintype "bidirectional"))
      (node (ref "R222") (pin "P$2") (pinfunction "P$2_P$2") (pintype "bidirectional"))
      (node (ref "U204") (pin "4") (pinfunction "4_4") (pintype "bidirectional"))
      (node (ref "U208") (pin "3") (pinfunction "A_3") (pintype "input"))
    )
    (net (code "110") (name "Net-(U301-FB)") (class "Default")
      (node (ref "R303") (pin "P$1") (pinfunction "P$1_P$1") (pintype "bidirectional"))
      (node (ref "R304") (pin "P$2") (pinfunction "P$2_P$2") (pintype "bidirectional"))
      (node (ref "U301") (pin "1") (pinfunction "FB_1") (pintype "bidirectional"))
    )
    (net (code "111") (name "Net-(U301-ISET)") (class "Default")
      (node (ref "R301") (pin "P$1") (pinfunction "P$1_P$1") (pintype "bidirectional"))
      (node (ref "R302") (pin "P$2") (pinfunction "P$2_P$2") (pintype "bidirectional"))
      (node (ref "U301") (pin "3") (pinfunction "ISET_3") (pintype "bidirectional"))
    )
    (net (code "112") (name "Net-(U401-VDDA)") (class "Default")
      (node (ref "C417") (pin "P$1") (pinfunction "P$1_P$1") (pintype "bidirectional"))
      (node (ref "D401") (pin "C") (pinfunction "C_C") (pintype "passive"))
      (node (ref "U401") (pin "16") (pinfunction "VDDA_16") (pintype "bidirectional"))
    )
    (net (code "113") (name "Net-(U401-VOA)") (class "Default")
      (node (ref "R413") (pin "P$1") (pinfunction "P$1_P$1") (pintype "bidirectional"))
      (node (ref "U401") (pin "15") (pinfunction "VOA_15") (pintype "bidirectional"))
    )
    (net (code "114") (name "Net-(U401-VOB)") (class "Default")
      (node (ref "R417") (pin "P$1") (pinfunction "P$1_P$1") (pintype "bidirectional"))
      (node (ref "U401") (pin "10") (pinfunction "VOB_10") (pintype "bidirectional"))
    )
    (net (code "115") (name "Net-(U402-VDDA)") (class "Default")
      (node (ref "C418") (pin "P$1") (pinfunction "P$1_P$1") (pintype "bidirectional"))
      (node (ref "D402") (pin "C") (pinfunction "C_C") (pintype "passive"))
      (node (ref "U402") (pin "16") (pinfunction "VDDA_16") (pintype "bidirectional"))
    )
    (net (code "116") (name "Net-(U402-VOA)") (class "Default")
      (node (ref "R414") (pin "P$1") (pinfunction "P$1_P$1") (pintype "bidirectional"))
      (node (ref "U402") (pin "15") (pinfunction "VOA_15") (pintype "bidirectional"))
    )
    (net (code "117") (name "Net-(U402-VOB)") (class "Default")
      (node (ref "R418") (pin "P$1") (pinfunction "P$1_P$1") (pintype "bidirectional"))
      (node (ref "U402") (pin "10") (pinfunction "VOB_10") (pintype "bidirectional"))
    )
    (net (code "118") (name "Net-(U403-VDDA)") (class "Default")
      (node (ref "C419") (pin "P$1") (pinfunction "P$1_P$1") (pintype "bidirectional"))
      (node (ref "D403") (pin "C") (pinfunction "C_C") (pintype "passive"))
      (node (ref "U403") (pin "16") (pinfunction "VDDA_16") (pintype "bidirectional"))
    )
    (net (code "119") (name "Net-(U403-VOA)") (class "Default")
      (node (ref "R415") (pin "P$1") (pinfunction "P$1_P$1") (pintype "bidirectional"))
      (node (ref "U403") (pin "15") (pinfunction "VOA_15") (pintype "bidirectional"))
    )
    (net (code "120") (name "Net-(U403-VOB)") (class "Default")
      (node (ref "R419") (pin "P$1") (pinfunction "P$1_P$1") (pintype "bidirectional"))
      (node (ref "U403") (pin "10") (pinfunction "VOB_10") (pintype "bidirectional"))
    )
    (net (code "121") (name "Net-(U404-VDDA)") (class "Default")
      (node (ref "C420") (pin "P$1") (pinfunction "P$1_P$1") (pintype "bidirectional"))
      (node (ref "D404") (pin "C") (pinfunction "C_C") (pintype "passive"))
      (node (ref "U404") (pin "16") (pinfunction "VDDA_16") (pintype "bidirectional"))
    )
    (net (code "122") (name "Net-(U404-VOA)") (class "Default")
      (node (ref "R416") (pin "P$1") (pinfunction "P$1_P$1") (pintype "bidirectional"))
      (node (ref "U404") (pin "15") (pinfunction "VOA_15") (pintype "bidirectional"))
    )
    (net (code "123") (name "Net-(U404-VOB)") (class "Default")
      (node (ref "R420") (pin "P$1") (pinfunction "P$1_P$1") (pintype "bidirectional"))
      (node (ref "U404") (pin "10") (pinfunction "VOB_10") (pintype "bidirectional"))
    )
    (net (code "124") (name "Net-(U405E-IN+)") (class "Default")
      (node (ref "C427") (pin "P$2") (pinfunction "P$2_P$2") (pintype "bidirectional"))
      (node (ref "C428") (pin "P$1") (pinfunction "P$1_P$1") (pintype "bidirectional"))
      (node (ref "R424") (pin "P$2") (pinfunction "P$2_P$2") (pintype "bidirectional"))
      (node (ref "U405") (pin "8") (pinfunction "IN+_8") (pintype "bidirectional"))
    )
    (net (code "125") (name "Net-(U405E-IN-)") (class "Default")
      (node (ref "C426") (pin "P$2") (pinfunction "P$2_P$2") (pintype "bidirectional"))
      (node (ref "C427") (pin "P$1") (pinfunction "P$1_P$1") (pintype "bidirectional"))
      (node (ref "R423") (pin "P$2") (pinfunction "P$2_P$2") (pintype "bidirectional"))
      (node (ref "U405") (pin "1") (pinfunction "IN-_1") (pintype "bidirectional"))
    )
    (net (code "126") (name "Net-(U406E-IN+)") (class "Default")
      (node (ref "C430") (pin "P$2") (pinfunction "P$2_P$2") (pintype "bidirectional"))
      (node (ref "C431") (pin "P$1") (pinfunction "P$1_P$1") (pintype "bidirectional"))
      (node (ref "R426") (pin "P$2") (pinfunction "P$2_P$2") (pintype "bidirectional"))
      (node (ref "U406") (pin "8") (pinfunction "IN+_8") (pintype "bidirectional"))
    )
    (net (code "127") (name "Net-(U406E-IN-)") (class "Default")
      (node (ref "C429") (pin "P$2") (pinfunction "P$2_P$2") (pintype "bidirectional"))
      (node (ref "C430") (pin "P$1") (pinfunction "P$1_P$1") (pintype "bidirectional"))
      (node (ref "R425") (pin "P$2") (pinfunction "P$2_P$2") (pintype "bidirectional"))
      (node (ref "U406") (pin "1") (pinfunction "IN-_1") (pintype "bidirectional"))
    )
    (net (code "128") (name "Net-(U407-AN)") (class "Default")
      (node (ref "R429") (pin "P$1") (pinfunction "P$1_P$1") (pintype "bidirectional"))
      (node (ref "U407") (pin "2") (pinfunction "AN_2") (pintype "bidirectional"))
    )
    (net (code "129") (name "Net-(U501-(CTS)GPIO4-~{CS4}-EVTCNTR)") (class "Default")
      (node (ref "JP507") (pin "1") (pinfunction "1_1") (pintype "passive"))
      (node (ref "U501") (pin "18") (pinfunction "(CTS)GPIO4-~{CS4}-EVTCNTR_18") (pintype "bidirectional"))
    )
    (net (code "130") (name "Net-(U501-(DCD)MISO)") (class "Default")
      (node (ref "JP501") (pin "1") (pinfunction "1_1") (pintype "passive"))
      (node (ref "U501") (pin "24") (pinfunction "(DCD)MISO_24") (pintype "bidirectional"))
    )
    (net (code "131") (name "Net-(U501-(DSR)GPIO0-~{CS0})") (class "Default")
      (node (ref "JP504") (pin "1") (pinfunction "1_1") (pintype "passive"))
      (node (ref "U501") (pin "22") (pinfunction "(DSR)GPIO0-~{CS0}_22") (pintype "bidirectional"))
    )
    (net (code "132") (name "Net-(U501-(DTR)MOSI)") (class "Default")
      (node (ref "JP502") (pin "1") (pinfunction "1_1") (pintype "passive"))
      (node (ref "U501") (pin "23") (pinfunction "(DTR)MOSI_23") (pintype "bidirectional"))
    )
    (net (code "133") (name "Net-(U501-(RI{slash}CLK)SCK)") (class "Default")
      (node (ref "JP503") (pin "1") (pinfunction "1_1") (pintype "passive"))
      (node (ref "U501") (pin "1") (pinfunction "(RI/CLK)SCK_1") (pintype "bidirectional"))
    )
    (net (code "134") (name "Net-(U501-(RXD)GPIO2-~{CS2})") (class "Default")
      (node (ref "JP506") (pin "1") (pinfunction "1_1") (pintype "passive"))
      (node (ref "U501") (pin "20") (pinfunction "(RXD)GPIO2-~{CS2}_20") (pintype "bidirectional"))
    )
    (net (code "135") (name "Net-(U501-(TXD)GPIO1-~{CS1})") (class "Default")
      (node (ref "JP505") (pin "1") (pinfunction "1_1") (pintype "passive"))
      (node (ref "U501") (pin "21") (pinfunction "(TXD)GPIO1-~{CS1}_21") (pintype "bidirectional"))
    )
    (net (code "136") (name "Net-(U501-VPP)") (class "Default")
      (node (ref "C503") (pin "P$1") (pinfunction "P$1_P$1") (pintype "bidirectional"))
      (node (ref "U501") (pin "16") (pinfunction "VPP_16") (pintype "bidirectional"))
    )
    (net (code "137") (name "Net-(U501-~{RST})") (class "Default")
      (node (ref "R501") (pin "P$2") (pinfunction "P$2_P$2") (pintype "bidirectional"))
      (node (ref "U501") (pin "9") (pinfunction "~{RST}_9") (pintype "bidirectional"))
    )
    (net (code "138") (name "PWM_IN") (class "Default")
      (node (ref "D504") (pin "P$3") (pinfunction "3_P$3") (pintype "bidirectional"))
      (node (ref "R504") (pin "P$2") (pinfunction "P$2_P$2") (pintype "bidirectional"))
      (node (ref "R505") (pin "P$2") (pinfunction "P$2_P$2") (pintype "bidirectional"))
      (node (ref "U102") (pin "58") (pinfunction "PWM_IN_58") (pintype "bidirectional"))
    )
    (net (code "139") (name "PWM_UX1_H") (class "Default")
      (node (ref "R405") (pin "P$2") (pinfunction "P$2_P$2") (pintype "bidirectional"))
      (node (ref "U102") (pin "39") (pinfunction "PWM_UX1_H_39") (pintype "bidirectional"))
      (node (ref "U401") (pin "1") (pinfunction "VIA_1") (pintype "bidirectional"))
    )
    (net (code "140") (name "PWM_UX1_L") (class "Default")
      (node (ref "R401") (pin "P$2") (pinfunction "P$2_P$2") (pintype "bidirectional"))
      (node (ref "U102") (pin "40") (pinfunction "PWM_UX1_L_40") (pintype "bidirectional"))
      (node (ref "U401") (pin "2") (pinfunction "VIB_2") (pintype "bidirectional"))
    )
    (net (code "141") (name "PWM_VX2_H") (class "Default")
      (node (ref "R406") (pin "P$2") (pinfunction "P$2_P$2") (pintype "bidirectional"))
      (node (ref "U102") (pin "41") (pinfunction "PWM_VX2_H_41") (pintype "bidirectional"))
      (node (ref "U402") (pin "1") (pinfunction "VIA_1") (pintype "bidirectional"))
    )
    (net (code "142") (name "PWM_VX2_L") (class "Default")
      (node (ref "R402") (pin "P$2") (pinfunction "P$2_P$2") (pintype "bidirectional"))
      (node (ref "U102") (pin "42") (pinfunction "PWM_VX2_L_42") (pintype "bidirectional"))
      (node (ref "U402") (pin "2") (pinfunction "VIB_2") (pintype "bidirectional"))
    )
    (net (code "143") (name "PWM_WY1_H") (class "Default")
      (node (ref "R407") (pin "P$2") (pinfunction "P$2_P$2") (pintype "bidirectional"))
      (node (ref "U102") (pin "46") (pinfunction "PWM_WY1_H_46") (pintype "bidirectional"))
      (node (ref "U403") (pin "1") (pinfunction "VIA_1") (pintype "bidirectional"))
    )
    (net (code "144") (name "PWM_WY1_L") (class "Default")
      (node (ref "R403") (pin "P$2") (pinfunction "P$2_P$2") (pintype "bidirectional"))
      (node (ref "U102") (pin "47") (pinfunction "PWM_WY1_L_47") (pintype "bidirectional"))
      (node (ref "U403") (pin "2") (pinfunction "VIB_2") (pintype "bidirectional"))
    )
    (net (code "145") (name "PWM_Y2_H") (class "Default")
      (node (ref "R408") (pin "P$2") (pinfunction "P$2_P$2") (pintype "bidirectional"))
      (node (ref "U102") (pin "48") (pinfunction "PWM_Y2_H_48") (pintype "bidirectional"))
      (node (ref "U404") (pin "1") (pinfunction "VIA_1") (pintype "bidirectional"))
    )
    (net (code "146") (name "PWM_Y2_L") (class "Default")
      (node (ref "R404") (pin "P$2") (pinfunction "P$2_P$2") (pintype "bidirectional"))
      (node (ref "U102") (pin "49") (pinfunction "PWM_Y2_L_49") (pintype "bidirectional"))
      (node (ref "U404") (pin "2") (pinfunction "VIB_2") (pintype "bidirectional"))
    )
    (net (code "147") (name "REF_H") (class "Default")
      (node (ref "U102") (pin "68") (pinfunction "REF_H_68") (pintype "bidirectional"))
      (node (ref "U208") (pin "5") (pinfunction "Y_5") (pintype "output"))
    )
    (net (code "148") (name "REF_L") (class "Default")
      (node (ref "U102") (pin "67") (pinfunction "REF_L_67") (pintype "bidirectional"))
      (node (ref "U208") (pin "2") (pinfunction "Y_2") (pintype "output"))
    )
    (net (code "149") (name "REF_R") (class "Default")
      (node (ref "U102") (pin "69") (pinfunction "REF_R_69") (pintype "bidirectional"))
      (node (ref "U208") (pin "7") (pinfunction "Y_7") (pintype "output"))
    )
    (net (code "150") (name "SCK") (class "Default")
      (node (ref "J501") (pin "2") (pinfunction "S_2") (pintype "passive"))
      (node (ref "JP503") (pin "2") (pinfunction "2_2") (pintype "passive"))
      (node (ref "U102") (pin "7") (pinfunction "SPI_SCK_7") (pintype "bidirectional"))
    )
    (net (code "151") (name "STEP") (class "Default")
      (node (ref "D506") (pin "P$3") (pinfunction "3_P$3") (pintype "bidirectional"))
      (node (ref "R509") (pin "P$2") (pinfunction "P$2_P$2") (pintype "bidirectional"))
      (node (ref "R510") (pin "P$2") (pinfunction "P$2_P$2") (pintype "bidirectional"))
      (node (ref "U102") (pin "57") (pinfunction "STP_57") (pintype "bidirectional"))
    )
    (net (code "152") (name "UX1") (class "Default")
      (node (ref "C417") (pin "P$2") (pinfunction "P$2_P$2") (pintype "bidirectional"))
      (node (ref "Q401") (pin "S1") (pinfunction "S1_S1") (pintype "bidirectional"))
      (node (ref "Q401") (pin "S2") (pinfunction "S1_S2") (pintype "bidirectional"))
      (node (ref "Q401") (pin "S3") (pinfunction "S1_S3") (pintype "bidirectional"))
      (node (ref "Q401") (pin "S4") (pinfunction "S1_S4") (pintype "bidirectional"))
      (node (ref "Q401") (pin "S5") (pinfunction "S1_S5") (pintype "bidirectional"))
      (node (ref "Q405") (pin "D1") (pinfunction "D1_D1") (pintype "bidirectional"))
      (node (ref "Q405") (pin "D2") (pinfunction "D1_D2") (pintype "bidirectional"))
      (node (ref "Q405") (pin "D3") (pinfunction "D1_D3") (pintype "bidirectional"))
      (node (ref "Q405") (pin "D4") (pinfunction "D1_D4") (pintype "bidirectional"))
      (node (ref "R421") (pin "1") (pinfunction "P$1_1") (pintype "bidirectional"))
      (node (ref "R421") (pin "2") (pinfunction "P$1_2") (pintype "bidirectional"))
      (node (ref "U401") (pin "14") (pinfunction "GNDA_14") (pintype "bidirectional"))
    )
    (net (code "153") (name "UX1@J401") (class "Default")
      (node (ref "J401") (pin "1") (pinfunction "S_1") (pintype "passive"))
      (node (ref "P403") (pin "H1") (pinfunction "S_H1") (pintype "passive"))
      (node (ref "P403") (pin "H10") (pinfunction "S_H10") (pintype "passive"))
      (node (ref "P403") (pin "H11") (pinfunction "S_H11") (pintype "passive"))
      (node (ref "P403") (pin "H12") (pinfunction "S_H12") (pintype "passive"))
      (node (ref "P403") (pin "H2") (pinfunction "S_H2") (pintype "passive"))
      (node (ref "P403") (pin "H3") (pinfunction "S_H3") (pintype "passive"))
      (node (ref "P403") (pin "H4") (pinfunction "S_H4") (pintype "passive"))
      (node (ref "P403") (pin "H5") (pinfunction "S_H5") (pintype "passive"))
      (node (ref "P403") (pin "H6") (pinfunction "S_H6") (pintype "passive"))
      (node (ref "P403") (pin "H7") (pinfunction "S_H7") (pintype "passive"))
      (node (ref "P403") (pin "H8") (pinfunction "S_H8") (pintype "passive"))
      (node (ref "P403") (pin "H9") (pinfunction "S_H9") (pintype "passive"))
      (node (ref "P403") (pin "PAD") (pinfunction "S_PAD") (pintype "passive"))
      (node (ref "R421") (pin "3") (pinfunction "P$2_3") (pintype "bidirectional"))
      (node (ref "R421") (pin "4") (pinfunction "P$2_4") (pintype "bidirectional"))
    )
    (net (code "154") (name "VBUS") (class "Default")
      (node (ref "R506") (pin "P$2") (pinfunction "P$2_P$2") (pintype "bidirectional"))
      (node (ref "R507") (pin "P$1") (pinfunction "P$1_P$1") (pintype "bidirectional"))
      (node (ref "U501") (pin "8") (pinfunction "VBUS_8") (pintype "bidirectional"))
    )
    (net (code "155") (name "VX2") (class "Default")
      (node (ref "C418") (pin "P$2") (pinfunction "P$2_P$2") (pintype "bidirectional"))
      (node (ref "J401") (pin "2") (pinfunction "S_2") (pintype "passive"))
      (node (ref "P401") (pin "H1") (pinfunction "S_H1") (pintype "passive"))
      (node (ref "P401") (pin "H10") (pinfunction "S_H10") (pintype "passive"))
      (node (ref "P401") (pin "H11") (pinfunction "S_H11") (pintype "passive"))
      (node (ref "P401") (pin "H12") (pinfunction "S_H12") (pintype "passive"))
      (node (ref "P401") (pin "H2") (pinfunction "S_H2") (pintype "passive"))
      (node (ref "P401") (pin "H3") (pinfunction "S_H3") (pintype "passive"))
      (node (ref "P401") (pin "H4") (pinfunction "S_H4") (pintype "passive"))
      (node (ref "P401") (pin "H5") (pinfunction "S_H5") (pintype "passive"))
      (node (ref "P401") (pin "H6") (pinfunction "S_H6") (pintype "passive"))
      (node (ref "P401") (pin "H7") (pinfunction "S_H7") (pintype "passive"))
      (node (ref "P401") (pin "H8") (pinfunction "S_H8") (pintype "passive"))
      (node (ref "P401") (pin "H9") (pinfunction "S_H9") (pintype "passive"))
      (node (ref "P401") (pin "PAD") (pinfunction "S_PAD") (pintype "passive"))
      (node (ref "Q402") (pin "S1") (pinfunction "S1_S1") (pintype "bidirectional"))
      (node (ref "Q402") (pin "S2") (pinfunction "S1_S2") (pintype "bidirectional"))
      (node (ref "Q402") (pin "S3") (pinfunction "S1_S3") (pintype "bidirectional"))
      (node (ref "Q402") (pin "S4") (pinfunction "S1_S4") (pintype "bidirectional"))
      (node (ref "Q402") (pin "S5") (pinfunction "S1_S5") (pintype "bidirectional"))
      (node (ref "Q406") (pin "D1") (pinfunction "D1_D1") (pintype "bidirectional"))
      (node (ref "Q406") (pin "D2") (pinfunction "D1_D2") (pintype "bidirectional"))
      (node (ref "Q406") (pin "D3") (pinfunction "D1_D3") (pintype "bidirectional"))
      (node (ref "Q406") (pin "D4") (pinfunction "D1_D4") (pintype "bidirectional"))
      (node (ref "U402") (pin "14") (pinfunction "GNDA_14") (pintype "bidirectional"))
    )
    (net (code "156") (name "WY1") (class "Default")
      (node (ref "C419") (pin "P$2") (pinfunction "P$2_P$2") (pintype "bidirectional"))
      (node (ref "Q403") (pin "S1") (pinfunction "S1_S1") (pintype "bidirectional"))
      (node (ref "Q403") (pin "S2") (pinfunction "S1_S2") (pintype "bidirectional"))
      (node (ref "Q403") (pin "S3") (pinfunction "S1_S3") (pintype "bidirectional"))
      (node (ref "Q403") (pin "S4") (pinfunction "S1_S4") (pintype "bidirectional"))
      (node (ref "Q403") (pin "S5") (pinfunction "S1_S5") (pintype "bidirectional"))
      (node (ref "Q407") (pin "D1") (pinfunction "D1_D1") (pintype "bidirectional"))
      (node (ref "Q407") (pin "D2") (pinfunction "D1_D2") (pintype "bidirectional"))
      (node (ref "Q407") (pin "D3") (pinfunction "D1_D3") (pintype "bidirectional"))
      (node (ref "Q407") (pin "D4") (pinfunction "D1_D4") (pintype "bidirectional"))
      (node (ref "R422") (pin "1") (pinfunction "P$1_1") (pintype "bidirectional"))
      (node (ref "R422") (pin "2") (pinfunction "P$1_2") (pintype "bidirectional"))
      (node (ref "U403") (pin "14") (pinfunction "GNDA_14") (pintype "bidirectional"))
    )
    (net (code "157") (name "WY1@J401") (class "Default")
      (node (ref "J401") (pin "3") (pinfunction "S_3") (pintype "passive"))
      (node (ref "P404") (pin "H1") (pinfunction "S_H1") (pintype "passive"))
      (node (ref "P404") (pin "H10") (pinfunction "S_H10") (pintype "passive"))
      (node (ref "P404") (pin "H11") (pinfunction "S_H11") (pintype "passive"))
      (node (ref "P404") (pin "H12") (pinfunction "S_H12") (pintype "passive"))
      (node (ref "P404") (pin "H2") (pinfunction "S_H2") (pintype "passive"))
      (node (ref "P404") (pin "H3") (pinfunction "S_H3") (pintype "passive"))
      (node (ref "P404") (pin "H4") (pinfunction "S_H4") (pintype "passive"))
      (node (ref "P404") (pin "H5") (pinfunction "S_H5") (pintype "passive"))
      (node (ref "P404") (pin "H6") (pinfunction "S_H6") (pintype "passive"))
      (node (ref "P404") (pin "H7") (pinfunction "S_H7") (pintype "passive"))
      (node (ref "P404") (pin "H8") (pinfunction "S_H8") (pintype "passive"))
      (node (ref "P404") (pin "H9") (pinfunction "S_H9") (pintype "passive"))
      (node (ref "P404") (pin "PAD") (pinfunction "S_PAD") (pintype "passive"))
      (node (ref "R422") (pin "3") (pinfunction "P$2_3") (pintype "bidirectional"))
      (node (ref "R422") (pin "4") (pinfunction "P$2_4") (pintype "bidirectional"))
    )
    (net (code "158") (name "Y2") (class "Default")
      (node (ref "C420") (pin "P$2") (pinfunction "P$2_P$2") (pintype "bidirectional"))
      (node (ref "J401") (pin "4") (pinfunction "S_4") (pintype "passive"))
      (node (ref "P402") (pin "H1") (pinfunction "S_H1") (pintype "passive"))
      (node (ref "P402") (pin "H10") (pinfunction "S_H10") (pintype "passive"))
      (node (ref "P402") (pin "H11") (pinfunction "S_H11") (pintype "passive"))
      (node (ref "P402") (pin "H12") (pinfunction "S_H12") (pintype "passive"))
      (node (ref "P402") (pin "H2") (pinfunction "S_H2") (pintype "passive"))
      (node (ref "P402") (pin "H3") (pinfunction "S_H3") (pintype "passive"))
      (node (ref "P402") (pin "H4") (pinfunction "S_H4") (pintype "passive"))
      (node (ref "P402") (pin "H5") (pinfunction "S_H5") (pintype "passive"))
      (node (ref "P402") (pin "H6") (pinfunction "S_H6") (pintype "passive"))
      (node (ref "P402") (pin "H7") (pinfunction "S_H7") (pintype "passive"))
      (node (ref "P402") (pin "H8") (pinfunction "S_H8") (pintype "passive"))
      (node (ref "P402") (pin "H9") (pinfunction "S_H9") (pintype "passive"))
      (node (ref "P402") (pin "PAD") (pinfunction "S_PAD") (pintype "passive"))
      (node (ref "Q404") (pin "S1") (pinfunction "S1_S1") (pintype "bidirectional"))
      (node (ref "Q404") (pin "S2") (pinfunction "S1_S2") (pintype "bidirectional"))
      (node (ref "Q404") (pin "S3") (pinfunction "S1_S3") (pintype "bidirectional"))
      (node (ref "Q404") (pin "S4") (pinfunction "S1_S4") (pintype "bidirectional"))
      (node (ref "Q404") (pin "S5") (pinfunction "S1_S5") (pintype "bidirectional"))
      (node (ref "Q408") (pin "D1") (pinfunction "D1_D1") (pintype "bidirectional"))
      (node (ref "Q408") (pin "D2") (pinfunction "D1_D2") (pintype "bidirectional"))
      (node (ref "Q408") (pin "D3") (pinfunction "D1_D3") (pintype "bidirectional"))
      (node (ref "Q408") (pin "D4") (pinfunction "D1_D4") (pintype "bidirectional"))
      (node (ref "U404") (pin "14") (pinfunction "GNDA_14") (pintype "bidirectional"))
    )
    (net (code "159") (name "unconnected-(J505C-S-Pad2)") (class "Default")
      (node (ref "J505") (pin "2") (pinfunction "S_2") (pintype "passive"))
    )
    (net (code "160") (name "unconnected-(U102A-GPIO0-Pad70)") (class "Default")
      (node (ref "U102") (pin "70") (pinfunction "GPIO0_70") (pintype "bidirectional"))
    )
    (net (code "161") (name "unconnected-(U102A-GPIO1-Pad71)") (class "Default")
      (node (ref "U102") (pin "71") (pinfunction "GPIO1_71") (pintype "bidirectional"))
    )
    (net (code "162") (name "unconnected-(U102A-GPIO2-Pad74)") (class "Default")
      (node (ref "U102") (pin "74") (pinfunction "GPIO2_74") (pintype "bidirectional"))
    )
    (net (code "163") (name "unconnected-(U201-Pad3)") (class "Default")
      (node (ref "U201") (pin "3") (pinfunction "3_3") (pintype "bidirectional"))
    )
    (net (code "164") (name "unconnected-(U202-Pad3)") (class "Default")
      (node (ref "U202") (pin "3") (pinfunction "3_3") (pintype "bidirectional"))
    )
    (net (code "165") (name "unconnected-(U203-Pad3)") (class "Default")
      (node (ref "U203") (pin "3") (pinfunction "3_3") (pintype "bidirectional"))
    )
    (net (code "166") (name "unconnected-(U204-Pad3)") (class "Default")
      (node (ref "U204") (pin "3") (pinfunction "3_3") (pintype "bidirectional"))
    )
    (net (code "167") (name "unconnected-(U501-(GPIO2-RS485)GPIO9-~{CS9}-SUSPEND-Pad12)") (class "Default")
      (node (ref "U501") (pin "12") (pinfunction "(GPIO2-RS485)GPIO9-~{CS9}-SUSPEND_12") (pintype "bidirectional"))
    )
    (net (code "168") (name "unconnected-(U501-(GPIO3-WKUP)GPIO10-~{CS10}-~{SUSPEND}-Pad11)") (class "Default")
      (node (ref "U501") (pin "11") (pinfunction "(GPIO3-WKUP)GPIO10-~{CS10}-~{SUSPEND}_11") (pintype "bidirectional"))
    )
    (net (code "169") (name "unconnected-(U501-(RTS)GPIO3-~{CS3}-RTR-Pad19)") (class "Default")
      (node (ref "U501") (pin "19") (pinfunction "(RTS)GPIO3-~{CS3}-RTR_19") (pintype "bidirectional"))
    )
    (net (code "170") (name "unconnected-(U501-(SUSPEND)GPIO5-~{CS5}-CLKOUT-Pad17)") (class "Default")
      (node (ref "U501") (pin "17") (pinfunction "(SUSPEND)GPIO5-~{CS5}-CLKOUT_17") (pintype "bidirectional"))
    )
    (net (code "171") (name "unconnected-(U501-(~{SUSPEND})GPIO6-~{CS6}-Pad15)") (class "Default")
      (node (ref "U501") (pin "15") (pinfunction "(~{SUSPEND})GPIO6-~{CS6}_15") (pintype "bidirectional"))
    )
    (net (code "172") (name "~{CS}") (class "Default")
      (node (ref "J501") (pin "1") (pinfunction "S_1") (pintype "passive"))
      (node (ref "JP504") (pin "2") (pinfunction "2_2") (pintype "passive"))
      (node (ref "U102") (pin "6") (pinfunction "SPI_NSCS_6") (pintype "bidirectional"))
    )
  )
)
